# SchemaM02.net
KiCad netlist of a schematic drawn in Altium Designer
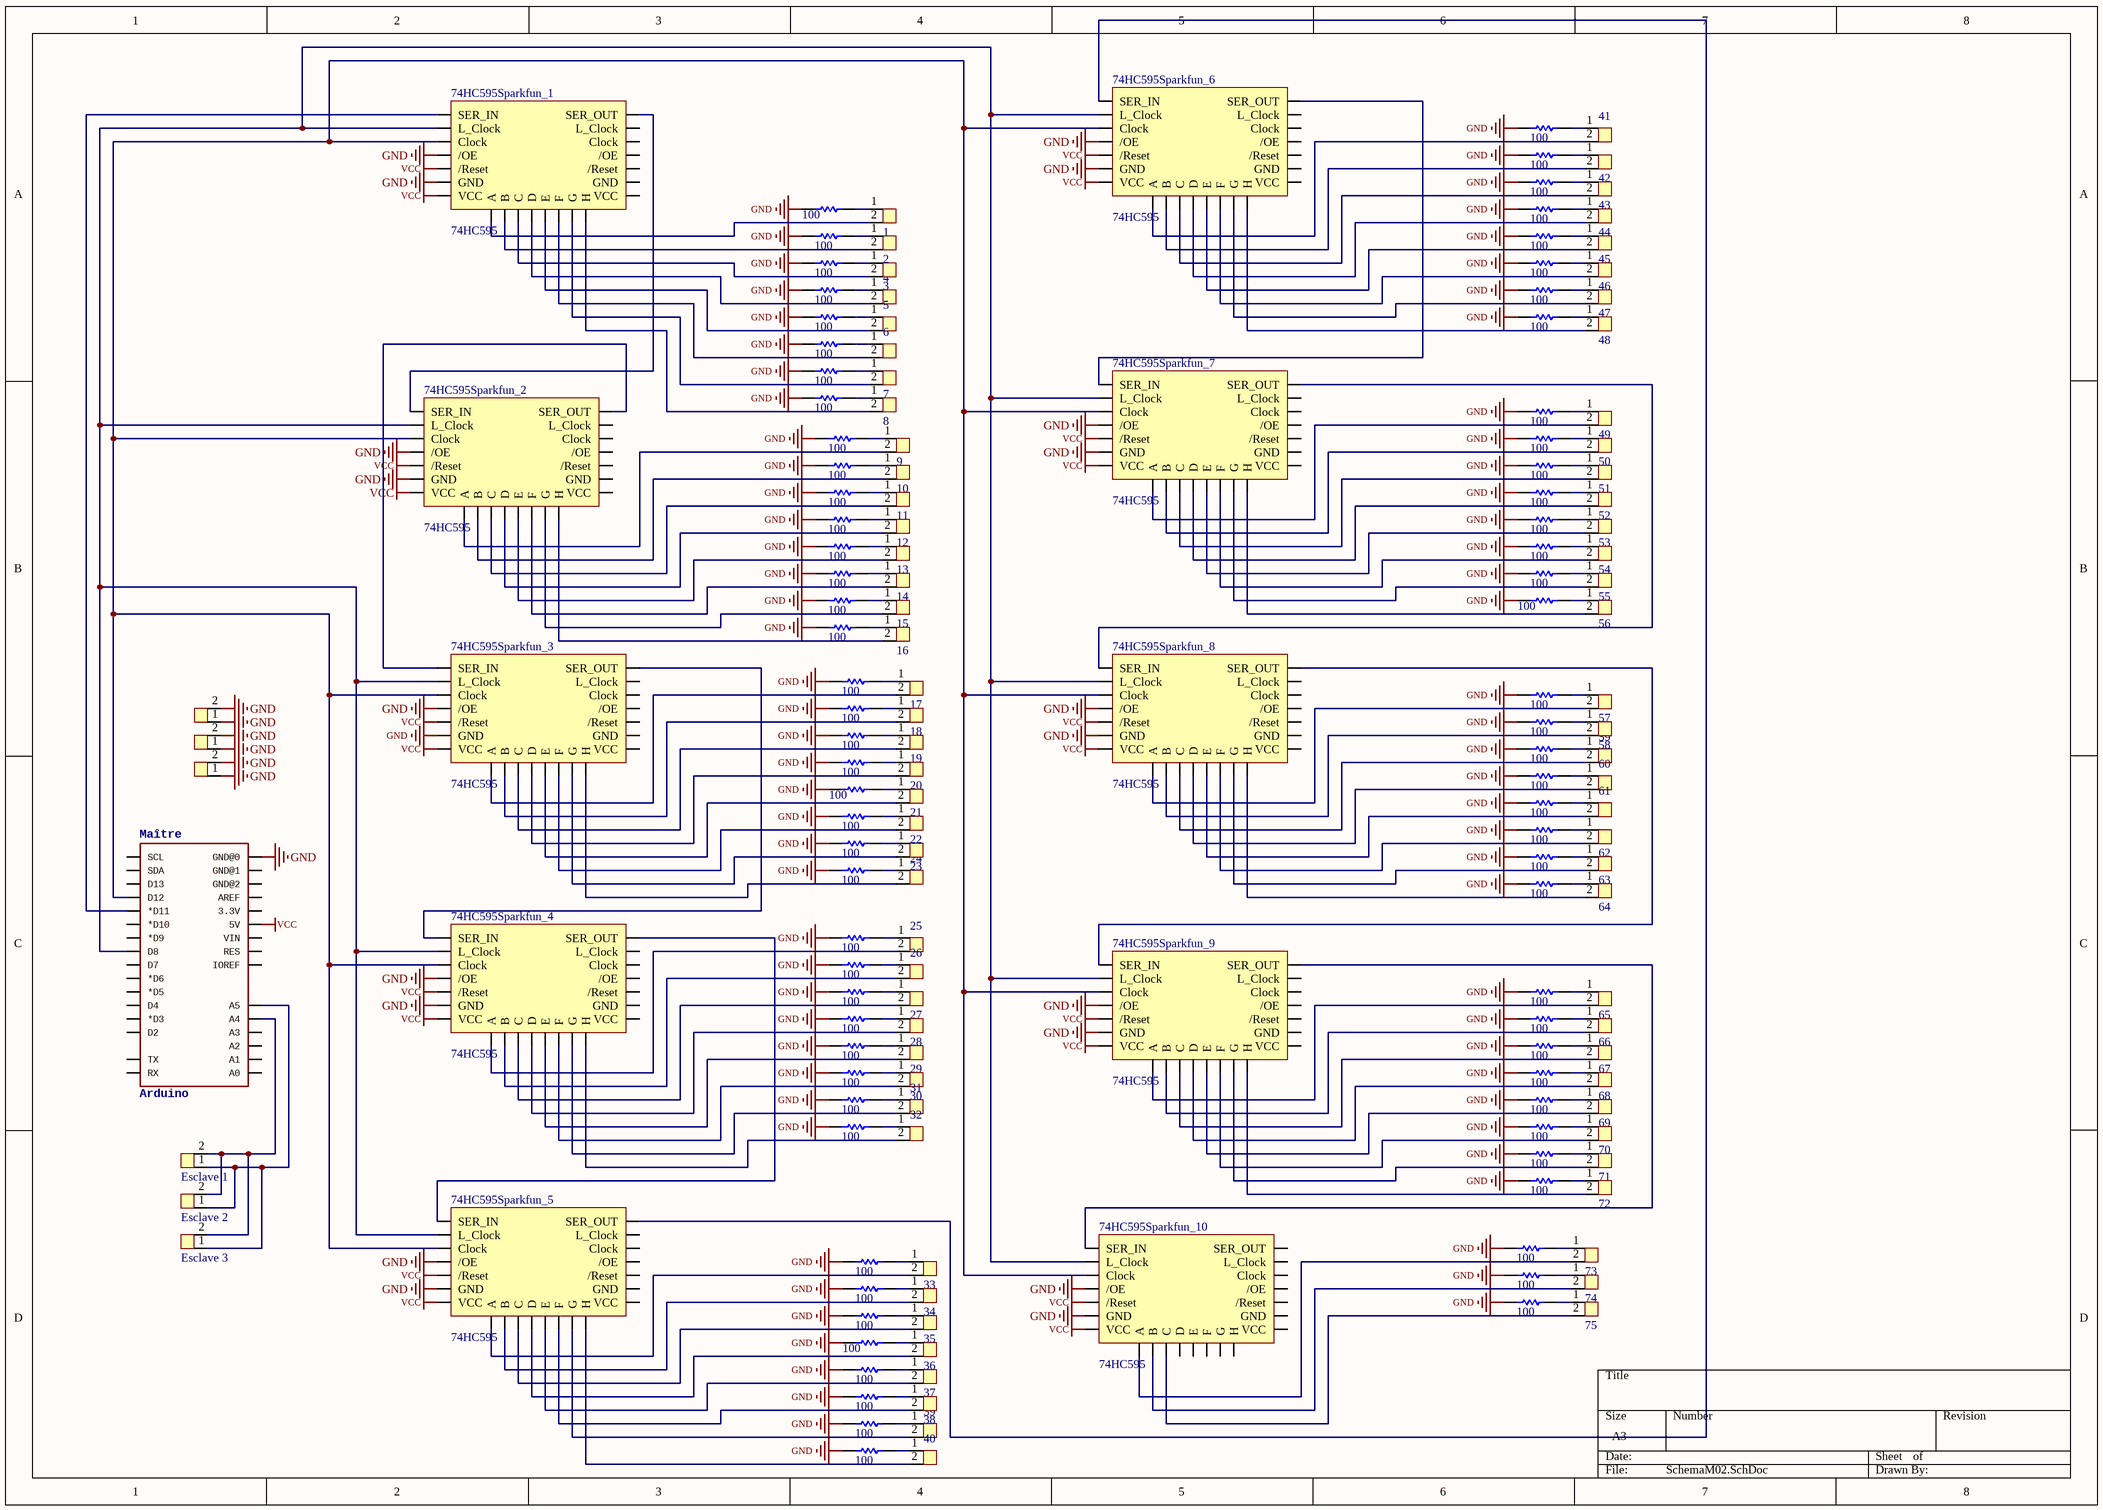
[diagram p0: SchemaM02.SchDoc]

(export (version "E")
  (design (tool "Eeschema 10.0.6"))
  (components
    (comp (ref "1")
      (value "Embase_CI_2_contacts")
      (footprint "Embase_CI_2_contacts")
      (libsource (lib "APISLibrary") (part "Embase_CI_2_contacts"))
    )
    (comp (ref "2")
      (value "Embase_CI_2_contacts")
      (footprint "Embase_CI_2_contacts")
      (libsource (lib "APISLibrary") (part "Embase_CI_2_contacts"))
    )
    (comp (ref "3")
      (value "Embase_CI_2_contacts")
      (footprint "Embase_CI_2_contacts")
      (libsource (lib "APISLibrary") (part "Embase_CI_2_contacts"))
    )
    (comp (ref "4")
      (value "Embase_CI_2_contacts")
      (footprint "Embase_CI_2_contacts")
      (libsource (lib "APISLibrary") (part "Embase_CI_2_contacts"))
    )
    (comp (ref "5")
      (value "Embase_CI_2_contacts")
      (footprint "Embase_CI_2_contacts")
      (libsource (lib "APISLibrary") (part "Embase_CI_2_contacts"))
    )
    (comp (ref "6")
      (value "Embase_CI_2_contacts")
      (footprint "Embase_CI_2_contacts")
      (libsource (lib "APISLibrary") (part "Embase_CI_2_contacts"))
    )
    (comp (ref "7")
      (value "Embase_CI_2_contacts")
      (footprint "Embase_CI_2_contacts")
      (libsource (lib "APISLibrary") (part "Embase_CI_2_contacts"))
    )
    (comp (ref "8")
      (value "Embase_CI_2_contacts")
      (footprint "Embase_CI_2_contacts")
      (libsource (lib "APISLibrary") (part "Embase_CI_2_contacts"))
    )
    (comp (ref "9")
      (value "Embase_CI_2_contacts")
      (footprint "Embase_CI_2_contacts")
      (libsource (lib "APISLibrary") (part "Embase_CI_2_contacts"))
    )
    (comp (ref "10")
      (value "Embase_CI_2_contacts")
      (footprint "Embase_CI_2_contacts")
      (libsource (lib "APISLibrary") (part "Embase_CI_2_contacts"))
    )
    (comp (ref "11")
      (value "Embase_CI_2_contacts")
      (footprint "Embase_CI_2_contacts")
      (libsource (lib "APISLibrary") (part "Embase_CI_2_contacts"))
    )
    (comp (ref "12")
      (value "Embase_CI_2_contacts")
      (footprint "Embase_CI_2_contacts")
      (libsource (lib "APISLibrary") (part "Embase_CI_2_contacts"))
    )
    (comp (ref "13")
      (value "Embase_CI_2_contacts")
      (footprint "Embase_CI_2_contacts")
      (libsource (lib "APISLibrary") (part "Embase_CI_2_contacts"))
    )
    (comp (ref "14")
      (value "Embase_CI_2_contacts")
      (footprint "Embase_CI_2_contacts")
      (libsource (lib "APISLibrary") (part "Embase_CI_2_contacts"))
    )
    (comp (ref "15")
      (value "Embase_CI_2_contacts")
      (footprint "Embase_CI_2_contacts")
      (libsource (lib "APISLibrary") (part "Embase_CI_2_contacts"))
    )
    (comp (ref "16")
      (value "Embase_CI_2_contacts")
      (footprint "Embase_CI_2_contacts")
      (libsource (lib "APISLibrary") (part "Embase_CI_2_contacts"))
    )
    (comp (ref "17")
      (value "Embase_CI_2_contacts")
      (footprint "Embase_CI_2_contacts")
      (libsource (lib "APISLibrary") (part "Embase_CI_2_contacts"))
    )
    (comp (ref "18")
      (value "Embase_CI_2_contacts")
      (footprint "Embase_CI_2_contacts")
      (libsource (lib "APISLibrary") (part "Embase_CI_2_contacts"))
    )
    (comp (ref "19")
      (value "Embase_CI_2_contacts")
      (footprint "Embase_CI_2_contacts")
      (libsource (lib "APISLibrary") (part "Embase_CI_2_contacts"))
    )
    (comp (ref "20")
      (value "Embase_CI_2_contacts")
      (footprint "Embase_CI_2_contacts")
      (libsource (lib "APISLibrary") (part "Embase_CI_2_contacts"))
    )
    (comp (ref "21")
      (value "Embase_CI_2_contacts")
      (footprint "Embase_CI_2_contacts")
      (libsource (lib "APISLibrary") (part "Embase_CI_2_contacts"))
    )
    (comp (ref "22")
      (value "Embase_CI_2_contacts")
      (footprint "Embase_CI_2_contacts")
      (libsource (lib "APISLibrary") (part "Embase_CI_2_contacts"))
    )
    (comp (ref "23")
      (value "Embase_CI_2_contacts")
      (footprint "Embase_CI_2_contacts")
      (libsource (lib "APISLibrary") (part "Embase_CI_2_contacts"))
    )
    (comp (ref "24")
      (value "Embase_CI_2_contacts")
      (footprint "Embase_CI_2_contacts")
      (libsource (lib "APISLibrary") (part "Embase_CI_2_contacts"))
    )
    (comp (ref "25")
      (value "Embase_CI_2_contacts")
      (footprint "Embase_CI_2_contacts")
      (libsource (lib "APISLibrary") (part "Embase_CI_2_contacts"))
    )
    (comp (ref "26")
      (value "Embase_CI_2_contacts")
      (footprint "Embase_CI_2_contacts")
      (libsource (lib "APISLibrary") (part "Embase_CI_2_contacts"))
    )
    (comp (ref "27")
      (value "Embase_CI_2_contacts")
      (footprint "Embase_CI_2_contacts")
      (libsource (lib "APISLibrary") (part "Embase_CI_2_contacts"))
    )
    (comp (ref "28")
      (value "Embase_CI_2_contacts")
      (footprint "Embase_CI_2_contacts")
      (libsource (lib "APISLibrary") (part "Embase_CI_2_contacts"))
    )
    (comp (ref "29")
      (value "Embase_CI_2_contacts")
      (footprint "Embase_CI_2_contacts")
      (libsource (lib "APISLibrary") (part "Embase_CI_2_contacts"))
    )
    (comp (ref "30")
      (value "Embase_CI_2_contacts")
      (footprint "Embase_CI_2_contacts")
      (libsource (lib "APISLibrary") (part "Embase_CI_2_contacts"))
    )
    (comp (ref "31")
      (value "Embase_CI_2_contacts")
      (footprint "Embase_CI_2_contacts")
      (libsource (lib "APISLibrary") (part "Embase_CI_2_contacts"))
    )
    (comp (ref "32")
      (value "Embase_CI_2_contacts")
      (footprint "Embase_CI_2_contacts")
      (libsource (lib "APISLibrary") (part "Embase_CI_2_contacts"))
    )
    (comp (ref "33")
      (value "Embase_CI_2_contacts")
      (footprint "Embase_CI_2_contacts")
      (libsource (lib "APISLibrary") (part "Embase_CI_2_contacts"))
    )
    (comp (ref "34")
      (value "Embase_CI_2_contacts")
      (footprint "Embase_CI_2_contacts")
      (libsource (lib "APISLibrary") (part "Embase_CI_2_contacts"))
    )
    (comp (ref "35")
      (value "Embase_CI_2_contacts")
      (footprint "Embase_CI_2_contacts")
      (libsource (lib "APISLibrary") (part "Embase_CI_2_contacts"))
    )
    (comp (ref "36")
      (value "Embase_CI_2_contacts")
      (footprint "Embase_CI_2_contacts")
      (libsource (lib "APISLibrary") (part "Embase_CI_2_contacts"))
    )
    (comp (ref "37")
      (value "Embase_CI_2_contacts")
      (footprint "Embase_CI_2_contacts")
      (libsource (lib "APISLibrary") (part "Embase_CI_2_contacts"))
    )
    (comp (ref "38")
      (value "Embase_CI_2_contacts")
      (footprint "Embase_CI_2_contacts")
      (libsource (lib "APISLibrary") (part "Embase_CI_2_contacts"))
    )
    (comp (ref "39")
      (value "Embase_CI_2_contacts")
      (footprint "Embase_CI_2_contacts")
      (libsource (lib "APISLibrary") (part "Embase_CI_2_contacts"))
    )
    (comp (ref "40")
      (value "Embase_CI_2_contacts")
      (footprint "Embase_CI_2_contacts")
      (libsource (lib "APISLibrary") (part "Embase_CI_2_contacts"))
    )
    (comp (ref "41")
      (value "Embase_CI_2_contacts")
      (footprint "Embase_CI_2_contacts")
      (libsource (lib "APISLibrary") (part "Embase_CI_2_contacts"))
    )
    (comp (ref "42")
      (value "Embase_CI_2_contacts")
      (footprint "Embase_CI_2_contacts")
      (libsource (lib "APISLibrary") (part "Embase_CI_2_contacts"))
    )
    (comp (ref "43")
      (value "Embase_CI_2_contacts")
      (footprint "Embase_CI_2_contacts")
      (libsource (lib "APISLibrary") (part "Embase_CI_2_contacts"))
    )
    (comp (ref "44")
      (value "Embase_CI_2_contacts")
      (footprint "Embase_CI_2_contacts")
      (libsource (lib "APISLibrary") (part "Embase_CI_2_contacts"))
    )
    (comp (ref "45")
      (value "Embase_CI_2_contacts")
      (footprint "Embase_CI_2_contacts")
      (libsource (lib "APISLibrary") (part "Embase_CI_2_contacts"))
    )
    (comp (ref "46")
      (value "Embase_CI_2_contacts")
      (footprint "Embase_CI_2_contacts")
      (libsource (lib "APISLibrary") (part "Embase_CI_2_contacts"))
    )
    (comp (ref "47")
      (value "Embase_CI_2_contacts")
      (footprint "Embase_CI_2_contacts")
      (libsource (lib "APISLibrary") (part "Embase_CI_2_contacts"))
    )
    (comp (ref "48")
      (value "Embase_CI_2_contacts")
      (footprint "Embase_CI_2_contacts")
      (libsource (lib "APISLibrary") (part "Embase_CI_2_contacts"))
    )
    (comp (ref "49")
      (value "Embase_CI_2_contacts")
      (footprint "Embase_CI_2_contacts")
      (libsource (lib "APISLibrary") (part "Embase_CI_2_contacts"))
    )
    (comp (ref "50")
      (value "Embase_CI_2_contacts")
      (footprint "Embase_CI_2_contacts")
      (libsource (lib "APISLibrary") (part "Embase_CI_2_contacts"))
    )
    (comp (ref "51")
      (value "Embase_CI_2_contacts")
      (footprint "Embase_CI_2_contacts")
      (libsource (lib "APISLibrary") (part "Embase_CI_2_contacts"))
    )
    (comp (ref "52")
      (value "Embase_CI_2_contacts")
      (footprint "Embase_CI_2_contacts")
      (libsource (lib "APISLibrary") (part "Embase_CI_2_contacts"))
    )
    (comp (ref "53")
      (value "Embase_CI_2_contacts")
      (footprint "Embase_CI_2_contacts")
      (libsource (lib "APISLibrary") (part "Embase_CI_2_contacts"))
    )
    (comp (ref "54")
      (value "Embase_CI_2_contacts")
      (footprint "Embase_CI_2_contacts")
      (libsource (lib "APISLibrary") (part "Embase_CI_2_contacts"))
    )
    (comp (ref "55")
      (value "Embase_CI_2_contacts")
      (footprint "Embase_CI_2_contacts")
      (libsource (lib "APISLibrary") (part "Embase_CI_2_contacts"))
    )
    (comp (ref "56")
      (value "Embase_CI_2_contacts")
      (footprint "Embase_CI_2_contacts")
      (libsource (lib "APISLibrary") (part "Embase_CI_2_contacts"))
    )
    (comp (ref "57")
      (value "Embase_CI_2_contacts")
      (footprint "Embase_CI_2_contacts")
      (libsource (lib "APISLibrary") (part "Embase_CI_2_contacts"))
    )
    (comp (ref "58")
      (value "Embase_CI_2_contacts")
      (footprint "Embase_CI_2_contacts")
      (libsource (lib "APISLibrary") (part "Embase_CI_2_contacts"))
    )
    (comp (ref "59")
      (value "Embase_CI_2_contacts")
      (footprint "Embase_CI_2_contacts")
      (libsource (lib "APISLibrary") (part "Embase_CI_2_contacts"))
    )
    (comp (ref "60")
      (value "Embase_CI_2_contacts")
      (footprint "Embase_CI_2_contacts")
      (libsource (lib "APISLibrary") (part "Embase_CI_2_contacts"))
    )
    (comp (ref "61")
      (value "Embase_CI_2_contacts")
      (footprint "Embase_CI_2_contacts")
      (libsource (lib "APISLibrary") (part "Embase_CI_2_contacts"))
    )
    (comp (ref "62")
      (value "Embase_CI_2_contacts")
      (footprint "Embase_CI_2_contacts")
      (libsource (lib "APISLibrary") (part "Embase_CI_2_contacts"))
    )
    (comp (ref "63")
      (value "Embase_CI_2_contacts")
      (footprint "Embase_CI_2_contacts")
      (libsource (lib "APISLibrary") (part "Embase_CI_2_contacts"))
    )
    (comp (ref "64")
      (value "Embase_CI_2_contacts")
      (footprint "Embase_CI_2_contacts")
      (libsource (lib "APISLibrary") (part "Embase_CI_2_contacts"))
    )
    (comp (ref "65")
      (value "Embase_CI_2_contacts")
      (footprint "Embase_CI_2_contacts")
      (libsource (lib "APISLibrary") (part "Embase_CI_2_contacts"))
    )
    (comp (ref "66")
      (value "Embase_CI_2_contacts")
      (footprint "Embase_CI_2_contacts")
      (libsource (lib "APISLibrary") (part "Embase_CI_2_contacts"))
    )
    (comp (ref "67")
      (value "Embase_CI_2_contacts")
      (footprint "Embase_CI_2_contacts")
      (libsource (lib "APISLibrary") (part "Embase_CI_2_contacts"))
    )
    (comp (ref "68")
      (value "Embase_CI_2_contacts")
      (footprint "Embase_CI_2_contacts")
      (libsource (lib "APISLibrary") (part "Embase_CI_2_contacts"))
    )
    (comp (ref "69")
      (value "Embase_CI_2_contacts")
      (footprint "Embase_CI_2_contacts")
      (libsource (lib "APISLibrary") (part "Embase_CI_2_contacts"))
    )
    (comp (ref "70")
      (value "Embase_CI_2_contacts")
      (footprint "Embase_CI_2_contacts")
      (libsource (lib "APISLibrary") (part "Embase_CI_2_contacts"))
    )
    (comp (ref "71")
      (value "Embase_CI_2_contacts")
      (footprint "Embase_CI_2_contacts")
      (libsource (lib "APISLibrary") (part "Embase_CI_2_contacts"))
    )
    (comp (ref "72")
      (value "Embase_CI_2_contacts")
      (footprint "Embase_CI_2_contacts")
      (libsource (lib "APISLibrary") (part "Embase_CI_2_contacts"))
    )
    (comp (ref "73")
      (value "Embase_CI_2_contacts")
      (footprint "Embase_CI_2_contacts")
      (libsource (lib "APISLibrary") (part "Embase_CI_2_contacts"))
    )
    (comp (ref "74")
      (value "Embase_CI_2_contacts")
      (footprint "Embase_CI_2_contacts")
      (libsource (lib "APISLibrary") (part "Embase_CI_2_contacts"))
    )
    (comp (ref "74HC595Sparkfun_1")
      (value "74HC595")
      (footprint "74HC595")
      (libsource (lib "APISLibrary") (part "74HC595"))
    )
    (comp (ref "74HC595Sparkfun_2")
      (value "74HC595")
      (footprint "74HC595")
      (libsource (lib "APISLibrary") (part "74HC595"))
    )
    (comp (ref "74HC595Sparkfun_3")
      (value "74HC595")
      (footprint "74HC595")
      (libsource (lib "APISLibrary") (part "74HC595"))
    )
    (comp (ref "74HC595Sparkfun_4")
      (value "74HC595")
      (footprint "74HC595")
      (libsource (lib "APISLibrary") (part "74HC595"))
    )
    (comp (ref "74HC595Sparkfun_5")
      (value "74HC595")
      (footprint "74HC595")
      (libsource (lib "APISLibrary") (part "74HC595"))
    )
    (comp (ref "74HC595Sparkfun_6")
      (value "74HC595")
      (footprint "74HC595")
      (libsource (lib "APISLibrary") (part "74HC595"))
    )
    (comp (ref "74HC595Sparkfun_7")
      (value "74HC595")
      (footprint "74HC595")
      (libsource (lib "APISLibrary") (part "74HC595"))
    )
    (comp (ref "74HC595Sparkfun_8")
      (value "74HC595")
      (footprint "74HC595")
      (libsource (lib "APISLibrary") (part "74HC595"))
    )
    (comp (ref "74HC595Sparkfun_9")
      (value "74HC595")
      (footprint "74HC595")
      (libsource (lib "APISLibrary") (part "74HC595"))
    )
    (comp (ref "74HC595Sparkfun_10")
      (value "74HC595")
      (footprint "74HC595")
      (libsource (lib "APISLibrary") (part "74HC595"))
    )
    (comp (ref "75")
      (value "Embase_CI_2_contacts")
      (footprint "Embase_CI_2_contacts")
      (libsource (lib "APISLibrary") (part "Embase_CI_2_contacts"))
    )
    (comp (ref "Esclave 1")
      (value "Embase_CI_2_contacts")
      (footprint "Embase_CI_2_contacts")
      (libsource (lib "") (part "Embase_CI_2_contacts_1"))
    )
    (comp (ref "Esclave 2")
      (value "Embase_CI_2_contacts")
      (footprint "Embase_CI_2_contacts")
      (libsource (lib "") (part "Embase_CI_2_contacts_1"))
    )
    (comp (ref "Esclave 3")
      (value "Embase_CI_2_contacts")
      (footprint "Embase_CI_2_contacts")
      (libsource (lib "") (part "Embase_CI_2_contacts_1"))
    )
    (comp (ref "Esclave 4")
      (value "Embase_CI_2_contacts")
      (footprint "Embase_CI_2_contacts")
      (libsource (lib "") (part "Embase_CI_2_contacts_1"))
    )
    (comp (ref "Esclave 5")
      (value "Embase_CI_2_contacts")
      (footprint "Embase_CI_2_contacts")
      (libsource (lib "") (part "Embase_CI_2_contacts_1"))
    )
    (comp (ref "Esclave 6")
      (value "Embase_CI_2_contacts")
      (footprint "Embase_CI_2_contacts")
      (libsource (lib "") (part "Embase_CI_2_contacts_1"))
    )
    (comp (ref "Maître")
      (value "Arduino")
      (footprint "UNO_R3_SHIELD")
      (libsource (lib "SparkFun-Boards") (part "ARDUINO_R3_SHIELD"))
    )
    (comp (ref "R1")
      (value "100")
      (footprint "AXIAL-0.3")
      (description "Resistor")
      (fields (field (name "Comment") "Res1") (field (name "PUBLISHER") "Altium Limited"))
      (libsource (lib "Miscellaneous Devices") (part "Res1"))
    )
    (comp (ref "R2")
      (value "100")
      (footprint "AXIAL-0.3")
      (description "Resistor")
      (fields (field (name "Comment") "Res1") (field (name "PUBLISHER") "Altium Limited"))
      (libsource (lib "Miscellaneous Devices") (part "Res1"))
    )
    (comp (ref "R3")
      (value "100")
      (footprint "AXIAL-0.3")
      (description "Resistor")
      (fields (field (name "Comment") "Res1") (field (name "PUBLISHER") "Altium Limited"))
      (libsource (lib "Miscellaneous Devices") (part "Res1"))
    )
    (comp (ref "R4")
      (value "100")
      (footprint "AXIAL-0.3")
      (description "Resistor")
      (fields (field (name "Comment") "Res1") (field (name "PUBLISHER") "Altium Limited"))
      (libsource (lib "Miscellaneous Devices") (part "Res1"))
    )
    (comp (ref "R5")
      (value "100")
      (footprint "AXIAL-0.3")
      (description "Resistor")
      (fields (field (name "Comment") "Res1") (field (name "PUBLISHER") "Altium Limited"))
      (libsource (lib "Miscellaneous Devices") (part "Res1"))
    )
    (comp (ref "R6")
      (value "100")
      (footprint "AXIAL-0.3")
      (description "Resistor")
      (fields (field (name "Comment") "Res1") (field (name "PUBLISHER") "Altium Limited"))
      (libsource (lib "Miscellaneous Devices") (part "Res1"))
    )
    (comp (ref "R7")
      (value "100")
      (footprint "AXIAL-0.3")
      (description "Resistor")
      (fields (field (name "Comment") "Res1") (field (name "PUBLISHER") "Altium Limited"))
      (libsource (lib "Miscellaneous Devices") (part "Res1"))
    )
    (comp (ref "R8")
      (value "100")
      (footprint "AXIAL-0.3")
      (description "Resistor")
      (fields (field (name "Comment") "Res1") (field (name "PUBLISHER") "Altium Limited"))
      (libsource (lib "Miscellaneous Devices") (part "Res1"))
    )
    (comp (ref "R9")
      (value "100")
      (footprint "AXIAL-0.3")
      (description "Resistor")
      (fields (field (name "Comment") "Res1") (field (name "PUBLISHER") "Altium Limited"))
      (libsource (lib "Miscellaneous Devices") (part "Res1"))
    )
    (comp (ref "R10")
      (value "100")
      (footprint "AXIAL-0.3")
      (description "Resistor")
      (fields (field (name "Comment") "Res1") (field (name "PUBLISHER") "Altium Limited"))
      (libsource (lib "Miscellaneous Devices") (part "Res1"))
    )
    (comp (ref "R11")
      (value "100")
      (footprint "AXIAL-0.3")
      (description "Resistor")
      (fields (field (name "Comment") "Res1") (field (name "PUBLISHER") "Altium Limited"))
      (libsource (lib "Miscellaneous Devices") (part "Res1"))
    )
    (comp (ref "R12")
      (value "100")
      (footprint "AXIAL-0.3")
      (description "Resistor")
      (fields (field (name "Comment") "Res1") (field (name "PUBLISHER") "Altium Limited"))
      (libsource (lib "Miscellaneous Devices") (part "Res1"))
    )
    (comp (ref "R13")
      (value "100")
      (footprint "AXIAL-0.3")
      (description "Resistor")
      (fields (field (name "Comment") "Res1") (field (name "PUBLISHER") "Altium Limited"))
      (libsource (lib "Miscellaneous Devices") (part "Res1"))
    )
    (comp (ref "R14")
      (value "100")
      (footprint "AXIAL-0.3")
      (description "Resistor")
      (fields (field (name "Comment") "Res1") (field (name "PUBLISHER") "Altium Limited"))
      (libsource (lib "Miscellaneous Devices") (part "Res1"))
    )
    (comp (ref "R15")
      (value "100")
      (footprint "AXIAL-0.3")
      (description "Resistor")
      (fields (field (name "Comment") "Res1") (field (name "PUBLISHER") "Altium Limited"))
      (libsource (lib "Miscellaneous Devices") (part "Res1"))
    )
    (comp (ref "R16")
      (value "100")
      (footprint "AXIAL-0.3")
      (description "Resistor")
      (fields (field (name "Comment") "Res1") (field (name "PUBLISHER") "Altium Limited"))
      (libsource (lib "Miscellaneous Devices") (part "Res1"))
    )
    (comp (ref "R17")
      (value "100")
      (footprint "AXIAL-0.3")
      (description "Resistor")
      (fields (field (name "Comment") "Res1") (field (name "PUBLISHER") "Altium Limited"))
      (libsource (lib "Miscellaneous Devices") (part "Res1"))
    )
    (comp (ref "R18")
      (value "100")
      (footprint "AXIAL-0.3")
      (description "Resistor")
      (fields (field (name "Comment") "Res1") (field (name "PUBLISHER") "Altium Limited"))
      (libsource (lib "Miscellaneous Devices") (part "Res1"))
    )
    (comp (ref "R19")
      (value "100")
      (footprint "AXIAL-0.3")
      (description "Resistor")
      (fields (field (name "Comment") "Res1") (field (name "PUBLISHER") "Altium Limited"))
      (libsource (lib "Miscellaneous Devices") (part "Res1"))
    )
    (comp (ref "R20")
      (value "100")
      (footprint "AXIAL-0.3")
      (description "Resistor")
      (fields (field (name "Comment") "Res1") (field (name "PUBLISHER") "Altium Limited"))
      (libsource (lib "Miscellaneous Devices") (part "Res1"))
    )
    (comp (ref "R21")
      (value "100")
      (footprint "AXIAL-0.3")
      (description "Resistor")
      (fields (field (name "Comment") "Res1") (field (name "PUBLISHER") "Altium Limited"))
      (libsource (lib "Miscellaneous Devices") (part "Res1"))
    )
    (comp (ref "R22")
      (value "100")
      (footprint "AXIAL-0.3")
      (description "Resistor")
      (fields (field (name "Comment") "Res1") (field (name "PUBLISHER") "Altium Limited"))
      (libsource (lib "Miscellaneous Devices") (part "Res1"))
    )
    (comp (ref "R23")
      (value "100")
      (footprint "AXIAL-0.3")
      (description "Resistor")
      (fields (field (name "Comment") "Res1") (field (name "PUBLISHER") "Altium Limited"))
      (libsource (lib "Miscellaneous Devices") (part "Res1"))
    )
    (comp (ref "R24")
      (value "100")
      (footprint "AXIAL-0.3")
      (description "Resistor")
      (fields (field (name "Comment") "Res1") (field (name "PUBLISHER") "Altium Limited"))
      (libsource (lib "Miscellaneous Devices") (part "Res1"))
    )
    (comp (ref "R25")
      (value "100")
      (footprint "AXIAL-0.3")
      (description "Resistor")
      (fields (field (name "Comment") "Res1") (field (name "PUBLISHER") "Altium Limited"))
      (libsource (lib "Miscellaneous Devices") (part "Res1"))
    )
    (comp (ref "R26")
      (value "100")
      (footprint "AXIAL-0.3")
      (description "Resistor")
      (fields (field (name "Comment") "Res1") (field (name "PUBLISHER") "Altium Limited"))
      (libsource (lib "Miscellaneous Devices") (part "Res1"))
    )
    (comp (ref "R27")
      (value "100")
      (footprint "AXIAL-0.3")
      (description "Resistor")
      (fields (field (name "Comment") "Res1") (field (name "PUBLISHER") "Altium Limited"))
      (libsource (lib "Miscellaneous Devices") (part "Res1"))
    )
    (comp (ref "R28")
      (value "100")
      (footprint "AXIAL-0.3")
      (description "Resistor")
      (fields (field (name "Comment") "Res1") (field (name "PUBLISHER") "Altium Limited"))
      (libsource (lib "Miscellaneous Devices") (part "Res1"))
    )
    (comp (ref "R29")
      (value "100")
      (footprint "AXIAL-0.3")
      (description "Resistor")
      (fields (field (name "Comment") "Res1") (field (name "PUBLISHER") "Altium Limited"))
      (libsource (lib "Miscellaneous Devices") (part "Res1"))
    )
    (comp (ref "R30")
      (value "100")
      (footprint "AXIAL-0.3")
      (description "Resistor")
      (fields (field (name "Comment") "Res1") (field (name "PUBLISHER") "Altium Limited"))
      (libsource (lib "Miscellaneous Devices") (part "Res1"))
    )
    (comp (ref "R31")
      (value "100")
      (footprint "AXIAL-0.3")
      (description "Resistor")
      (fields (field (name "Comment") "Res1") (field (name "PUBLISHER") "Altium Limited"))
      (libsource (lib "Miscellaneous Devices") (part "Res1"))
    )
    (comp (ref "R32")
      (value "100")
      (footprint "AXIAL-0.3")
      (description "Resistor")
      (fields (field (name "Comment") "Res1") (field (name "PUBLISHER") "Altium Limited"))
      (libsource (lib "Miscellaneous Devices") (part "Res1"))
    )
    (comp (ref "R33")
      (value "100")
      (footprint "AXIAL-0.3")
      (description "Resistor")
      (fields (field (name "Comment") "Res1") (field (name "PUBLISHER") "Altium Limited"))
      (libsource (lib "Miscellaneous Devices") (part "Res1"))
    )
    (comp (ref "R34")
      (value "100")
      (footprint "AXIAL-0.3")
      (description "Resistor")
      (fields (field (name "Comment") "Res1") (field (name "PUBLISHER") "Altium Limited"))
      (libsource (lib "Miscellaneous Devices") (part "Res1"))
    )
    (comp (ref "R35")
      (value "100")
      (footprint "AXIAL-0.3")
      (description "Resistor")
      (fields (field (name "Comment") "Res1") (field (name "PUBLISHER") "Altium Limited"))
      (libsource (lib "Miscellaneous Devices") (part "Res1"))
    )
    (comp (ref "R36")
      (value "100")
      (footprint "AXIAL-0.3")
      (description "Resistor")
      (fields (field (name "Comment") "Res1") (field (name "PUBLISHER") "Altium Limited"))
      (libsource (lib "Miscellaneous Devices") (part "Res1"))
    )
    (comp (ref "R37")
      (value "100")
      (footprint "AXIAL-0.3")
      (description "Resistor")
      (fields (field (name "Comment") "Res1") (field (name "PUBLISHER") "Altium Limited"))
      (libsource (lib "Miscellaneous Devices") (part "Res1"))
    )
    (comp (ref "R38")
      (value "100")
      (footprint "AXIAL-0.3")
      (description "Resistor")
      (fields (field (name "Comment") "Res1") (field (name "PUBLISHER") "Altium Limited"))
      (libsource (lib "Miscellaneous Devices") (part "Res1"))
    )
    (comp (ref "R39")
      (value "100")
      (footprint "AXIAL-0.3")
      (description "Resistor")
      (fields (field (name "Comment") "Res1") (field (name "PUBLISHER") "Altium Limited"))
      (libsource (lib "Miscellaneous Devices") (part "Res1"))
    )
    (comp (ref "R40")
      (value "100")
      (footprint "AXIAL-0.3")
      (description "Resistor")
      (fields (field (name "Comment") "Res1") (field (name "PUBLISHER") "Altium Limited"))
      (libsource (lib "Miscellaneous Devices") (part "Res1"))
    )
    (comp (ref "R41")
      (value "100")
      (footprint "AXIAL-0.3")
      (description "Resistor")
      (fields (field (name "Comment") "Res1") (field (name "PUBLISHER") "Altium Limited"))
      (libsource (lib "Miscellaneous Devices") (part "Res1"))
    )
    (comp (ref "R42")
      (value "100")
      (footprint "AXIAL-0.3")
      (description "Resistor")
      (fields (field (name "Comment") "Res1") (field (name "PUBLISHER") "Altium Limited"))
      (libsource (lib "Miscellaneous Devices") (part "Res1"))
    )
    (comp (ref "R43")
      (value "100")
      (footprint "AXIAL-0.3")
      (description "Resistor")
      (fields (field (name "Comment") "Res1") (field (name "PUBLISHER") "Altium Limited"))
      (libsource (lib "Miscellaneous Devices") (part "Res1"))
    )
    (comp (ref "R44")
      (value "100")
      (footprint "AXIAL-0.3")
      (description "Resistor")
      (fields (field (name "Comment") "Res1") (field (name "PUBLISHER") "Altium Limited"))
      (libsource (lib "Miscellaneous Devices") (part "Res1"))
    )
    (comp (ref "R45")
      (value "100")
      (footprint "AXIAL-0.3")
      (description "Resistor")
      (fields (field (name "Comment") "Res1") (field (name "PUBLISHER") "Altium Limited"))
      (libsource (lib "Miscellaneous Devices") (part "Res1"))
    )
    (comp (ref "R46")
      (value "100")
      (footprint "AXIAL-0.3")
      (description "Resistor")
      (fields (field (name "Comment") "Res1") (field (name "PUBLISHER") "Altium Limited"))
      (libsource (lib "Miscellaneous Devices") (part "Res1"))
    )
    (comp (ref "R47")
      (value "100")
      (footprint "AXIAL-0.3")
      (description "Resistor")
      (fields (field (name "Comment") "Res1") (field (name "PUBLISHER") "Altium Limited"))
      (libsource (lib "Miscellaneous Devices") (part "Res1"))
    )
    (comp (ref "R48")
      (value "100")
      (footprint "AXIAL-0.3")
      (description "Resistor")
      (fields (field (name "Comment") "Res1") (field (name "PUBLISHER") "Altium Limited"))
      (libsource (lib "Miscellaneous Devices") (part "Res1"))
    )
    (comp (ref "R49")
      (value "100")
      (footprint "AXIAL-0.3")
      (description "Resistor")
      (fields (field (name "Comment") "Res1") (field (name "PUBLISHER") "Altium Limited"))
      (libsource (lib "Miscellaneous Devices") (part "Res1"))
    )
    (comp (ref "R50")
      (value "100")
      (footprint "AXIAL-0.3")
      (description "Resistor")
      (fields (field (name "Comment") "Res1") (field (name "PUBLISHER") "Altium Limited"))
      (libsource (lib "Miscellaneous Devices") (part "Res1"))
    )
    (comp (ref "R51")
      (value "100")
      (footprint "AXIAL-0.3")
      (description "Resistor")
      (fields (field (name "Comment") "Res1") (field (name "PUBLISHER") "Altium Limited"))
      (libsource (lib "Miscellaneous Devices") (part "Res1"))
    )
    (comp (ref "R52")
      (value "100")
      (footprint "AXIAL-0.3")
      (description "Resistor")
      (fields (field (name "Comment") "Res1") (field (name "PUBLISHER") "Altium Limited"))
      (libsource (lib "Miscellaneous Devices") (part "Res1"))
    )
    (comp (ref "R53")
      (value "100")
      (footprint "AXIAL-0.3")
      (description "Resistor")
      (fields (field (name "Comment") "Res1") (field (name "PUBLISHER") "Altium Limited"))
      (libsource (lib "Miscellaneous Devices") (part "Res1"))
    )
    (comp (ref "R54")
      (value "100")
      (footprint "AXIAL-0.3")
      (description "Resistor")
      (fields (field (name "Comment") "Res1") (field (name "PUBLISHER") "Altium Limited"))
      (libsource (lib "Miscellaneous Devices") (part "Res1"))
    )
    (comp (ref "R55")
      (value "100")
      (footprint "AXIAL-0.3")
      (description "Resistor")
      (fields (field (name "Comment") "Res1") (field (name "PUBLISHER") "Altium Limited"))
      (libsource (lib "Miscellaneous Devices") (part "Res1"))
    )
    (comp (ref "R56")
      (value "100")
      (footprint "AXIAL-0.3")
      (description "Resistor")
      (fields (field (name "Comment") "Res1") (field (name "PUBLISHER") "Altium Limited"))
      (libsource (lib "Miscellaneous Devices") (part "Res1"))
    )
    (comp (ref "R57")
      (value "100")
      (footprint "AXIAL-0.3")
      (description "Resistor")
      (fields (field (name "Comment") "Res1") (field (name "PUBLISHER") "Altium Limited"))
      (libsource (lib "Miscellaneous Devices") (part "Res1"))
    )
    (comp (ref "R58")
      (value "100")
      (footprint "AXIAL-0.3")
      (description "Resistor")
      (fields (field (name "Comment") "Res1") (field (name "PUBLISHER") "Altium Limited"))
      (libsource (lib "Miscellaneous Devices") (part "Res1"))
    )
    (comp (ref "R59")
      (value "100")
      (footprint "AXIAL-0.3")
      (description "Resistor")
      (fields (field (name "Comment") "Res1") (field (name "PUBLISHER") "Altium Limited"))
      (libsource (lib "Miscellaneous Devices") (part "Res1"))
    )
    (comp (ref "R60")
      (value "100")
      (footprint "AXIAL-0.3")
      (description "Resistor")
      (fields (field (name "Comment") "Res1") (field (name "PUBLISHER") "Altium Limited"))
      (libsource (lib "Miscellaneous Devices") (part "Res1"))
    )
    (comp (ref "R61")
      (value "100")
      (footprint "AXIAL-0.3")
      (description "Resistor")
      (fields (field (name "Comment") "Res1") (field (name "PUBLISHER") "Altium Limited"))
      (libsource (lib "Miscellaneous Devices") (part "Res1"))
    )
    (comp (ref "R62")
      (value "100")
      (footprint "AXIAL-0.3")
      (description "Resistor")
      (fields (field (name "Comment") "Res1") (field (name "PUBLISHER") "Altium Limited"))
      (libsource (lib "Miscellaneous Devices") (part "Res1"))
    )
    (comp (ref "R63")
      (value "100")
      (footprint "AXIAL-0.3")
      (description "Resistor")
      (fields (field (name "Comment") "Res1") (field (name "PUBLISHER") "Altium Limited"))
      (libsource (lib "Miscellaneous Devices") (part "Res1"))
    )
    (comp (ref "R64")
      (value "100")
      (footprint "AXIAL-0.3")
      (description "Resistor")
      (fields (field (name "Comment") "Res1") (field (name "PUBLISHER") "Altium Limited"))
      (libsource (lib "Miscellaneous Devices") (part "Res1"))
    )
    (comp (ref "R65")
      (value "100")
      (footprint "AXIAL-0.3")
      (description "Resistor")
      (fields (field (name "Comment") "Res1") (field (name "PUBLISHER") "Altium Limited"))
      (libsource (lib "Miscellaneous Devices") (part "Res1"))
    )
    (comp (ref "R66")
      (value "100")
      (footprint "AXIAL-0.3")
      (description "Resistor")
      (fields (field (name "Comment") "Res1") (field (name "PUBLISHER") "Altium Limited"))
      (libsource (lib "Miscellaneous Devices") (part "Res1"))
    )
    (comp (ref "R67")
      (value "100")
      (footprint "AXIAL-0.3")
      (description "Resistor")
      (fields (field (name "Comment") "Res1") (field (name "PUBLISHER") "Altium Limited"))
      (libsource (lib "Miscellaneous Devices") (part "Res1"))
    )
    (comp (ref "R68")
      (value "100")
      (footprint "AXIAL-0.3")
      (description "Resistor")
      (fields (field (name "Comment") "Res1") (field (name "PUBLISHER") "Altium Limited"))
      (libsource (lib "Miscellaneous Devices") (part "Res1"))
    )
    (comp (ref "R69")
      (value "100")
      (footprint "AXIAL-0.3")
      (description "Resistor")
      (fields (field (name "Comment") "Res1") (field (name "PUBLISHER") "Altium Limited"))
      (libsource (lib "Miscellaneous Devices") (part "Res1"))
    )
    (comp (ref "R70")
      (value "100")
      (footprint "AXIAL-0.3")
      (description "Resistor")
      (fields (field (name "Comment") "Res1") (field (name "PUBLISHER") "Altium Limited"))
      (libsource (lib "Miscellaneous Devices") (part "Res1"))
    )
    (comp (ref "R71")
      (value "100")
      (footprint "AXIAL-0.3")
      (description "Resistor")
      (fields (field (name "Comment") "Res1") (field (name "PUBLISHER") "Altium Limited"))
      (libsource (lib "Miscellaneous Devices") (part "Res1"))
    )
    (comp (ref "R72")
      (value "100")
      (footprint "AXIAL-0.3")
      (description "Resistor")
      (fields (field (name "Comment") "Res1") (field (name "PUBLISHER") "Altium Limited"))
      (libsource (lib "Miscellaneous Devices") (part "Res1"))
    )
    (comp (ref "R73")
      (value "100")
      (footprint "AXIAL-0.3")
      (description "Resistor")
      (fields (field (name "Comment") "Res1") (field (name "PUBLISHER") "Altium Limited"))
      (libsource (lib "Miscellaneous Devices") (part "Res1"))
    )
    (comp (ref "R74")
      (value "100")
      (footprint "AXIAL-0.3")
      (description "Resistor")
      (fields (field (name "Comment") "Res1") (field (name "PUBLISHER") "Altium Limited"))
      (libsource (lib "Miscellaneous Devices") (part "Res1"))
    )
    (comp (ref "R75")
      (value "100")
      (footprint "AXIAL-0.3")
      (description "Resistor")
      (fields (field (name "Comment") "Res1") (field (name "PUBLISHER") "Altium Limited"))
      (libsource (lib "Miscellaneous Devices") (part "Res1"))
    )
  )
  (nets
    (net (code "1") (name "GND") (class "Default")
      (node (ref "74HC595Sparkfun_1") (pin "2") (pinfunction "GND_2") (pintype "passive"))
      (node (ref "74HC595Sparkfun_1") (pin "4") (pinfunction "/OE_4") (pintype "passive"))
      (node (ref "74HC595Sparkfun_10") (pin "2") (pinfunction "GND_2") (pintype "passive"))
      (node (ref "74HC595Sparkfun_10") (pin "4") (pinfunction "/OE_4") (pintype "passive"))
      (node (ref "74HC595Sparkfun_2") (pin "2") (pinfunction "GND_2") (pintype "passive"))
      (node (ref "74HC595Sparkfun_2") (pin "4") (pinfunction "/OE_4") (pintype "passive"))
      (node (ref "74HC595Sparkfun_3") (pin "2") (pinfunction "GND_2") (pintype "passive"))
      (node (ref "74HC595Sparkfun_3") (pin "4") (pinfunction "/OE_4") (pintype "passive"))
      (node (ref "74HC595Sparkfun_4") (pin "2") (pinfunction "GND_2") (pintype "passive"))
      (node (ref "74HC595Sparkfun_4") (pin "4") (pinfunction "/OE_4") (pintype "passive"))
      (node (ref "74HC595Sparkfun_5") (pin "2") (pinfunction "GND_2") (pintype "passive"))
      (node (ref "74HC595Sparkfun_5") (pin "4") (pinfunction "/OE_4") (pintype "passive"))
      (node (ref "74HC595Sparkfun_6") (pin "2") (pinfunction "GND_2") (pintype "passive"))
      (node (ref "74HC595Sparkfun_6") (pin "4") (pinfunction "/OE_4") (pintype "passive"))
      (node (ref "74HC595Sparkfun_7") (pin "2") (pinfunction "GND_2") (pintype "passive"))
      (node (ref "74HC595Sparkfun_7") (pin "4") (pinfunction "/OE_4") (pintype "passive"))
      (node (ref "74HC595Sparkfun_8") (pin "2") (pinfunction "GND_2") (pintype "passive"))
      (node (ref "74HC595Sparkfun_8") (pin "4") (pinfunction "/OE_4") (pintype "passive"))
      (node (ref "74HC595Sparkfun_9") (pin "2") (pinfunction "GND_2") (pintype "passive"))
      (node (ref "74HC595Sparkfun_9") (pin "4") (pinfunction "/OE_4") (pintype "passive"))
      (node (ref "Esclave 4") (pin "1") (pinfunction "1_1") (pintype "passive"))
      (node (ref "Esclave 4") (pin "2") (pinfunction "2_2") (pintype "passive"))
      (node (ref "Esclave 5") (pin "1") (pinfunction "1_1") (pintype "passive"))
      (node (ref "Esclave 5") (pin "2") (pinfunction "2_2") (pintype "passive"))
      (node (ref "Esclave 6") (pin "1") (pinfunction "1_1") (pintype "passive"))
      (node (ref "Esclave 6") (pin "2") (pinfunction "2_2") (pintype "passive"))
      (node (ref "Maître") (pin "GND@0") (pinfunction "GND@0_GND@0") (pintype "passive"))
      (node (ref "R1") (pin "1") (pinfunction "1_1") (pintype "passive"))
      (node (ref "R10") (pin "1") (pinfunction "1_1") (pintype "passive"))
      (node (ref "R11") (pin "1") (pinfunction "1_1") (pintype "passive"))
      (node (ref "R12") (pin "1") (pinfunction "1_1") (pintype "passive"))
      (node (ref "R13") (pin "1") (pinfunction "1_1") (pintype "passive"))
      (node (ref "R14") (pin "1") (pinfunction "1_1") (pintype "passive"))
      (node (ref "R15") (pin "1") (pinfunction "1_1") (pintype "passive"))
      (node (ref "R16") (pin "1") (pinfunction "1_1") (pintype "passive"))
      (node (ref "R17") (pin "1") (pinfunction "1_1") (pintype "passive"))
      (node (ref "R18") (pin "1") (pinfunction "1_1") (pintype "passive"))
      (node (ref "R19") (pin "1") (pinfunction "1_1") (pintype "passive"))
      (node (ref "R2") (pin "1") (pinfunction "1_1") (pintype "passive"))
      (node (ref "R20") (pin "1") (pinfunction "1_1") (pintype "passive"))
      (node (ref "R21") (pin "1") (pinfunction "1_1") (pintype "passive"))
      (node (ref "R22") (pin "1") (pinfunction "1_1") (pintype "passive"))
      (node (ref "R23") (pin "1") (pinfunction "1_1") (pintype "passive"))
      (node (ref "R24") (pin "1") (pinfunction "1_1") (pintype "passive"))
      (node (ref "R25") (pin "1") (pinfunction "1_1") (pintype "passive"))
      (node (ref "R26") (pin "1") (pinfunction "1_1") (pintype "passive"))
      (node (ref "R27") (pin "1") (pinfunction "1_1") (pintype "passive"))
      (node (ref "R28") (pin "1") (pinfunction "1_1") (pintype "passive"))
      (node (ref "R29") (pin "1") (pinfunction "1_1") (pintype "passive"))
      (node (ref "R3") (pin "1") (pinfunction "1_1") (pintype "passive"))
      (node (ref "R30") (pin "1") (pinfunction "1_1") (pintype "passive"))
      (node (ref "R31") (pin "1") (pinfunction "1_1") (pintype "passive"))
      (node (ref "R32") (pin "1") (pinfunction "1_1") (pintype "passive"))
      (node (ref "R33") (pin "1") (pinfunction "1_1") (pintype "passive"))
      (node (ref "R34") (pin "1") (pinfunction "1_1") (pintype "passive"))
      (node (ref "R35") (pin "1") (pinfunction "1_1") (pintype "passive"))
      (node (ref "R36") (pin "1") (pinfunction "1_1") (pintype "passive"))
      (node (ref "R37") (pin "1") (pinfunction "1_1") (pintype "passive"))
      (node (ref "R38") (pin "1") (pinfunction "1_1") (pintype "passive"))
      (node (ref "R39") (pin "1") (pinfunction "1_1") (pintype "passive"))
      (node (ref "R4") (pin "1") (pinfunction "1_1") (pintype "passive"))
      (node (ref "R40") (pin "1") (pinfunction "1_1") (pintype "passive"))
      (node (ref "R41") (pin "1") (pinfunction "1_1") (pintype "passive"))
      (node (ref "R42") (pin "1") (pinfunction "1_1") (pintype "passive"))
      (node (ref "R43") (pin "1") (pinfunction "1_1") (pintype "passive"))
      (node (ref "R44") (pin "1") (pinfunction "1_1") (pintype "passive"))
      (node (ref "R45") (pin "1") (pinfunction "1_1") (pintype "passive"))
      (node (ref "R46") (pin "1") (pinfunction "1_1") (pintype "passive"))
      (node (ref "R47") (pin "1") (pinfunction "1_1") (pintype "passive"))
      (node (ref "R48") (pin "1") (pinfunction "1_1") (pintype "passive"))
      (node (ref "R49") (pin "1") (pinfunction "1_1") (pintype "passive"))
      (node (ref "R5") (pin "1") (pinfunction "1_1") (pintype "passive"))
      (node (ref "R50") (pin "1") (pinfunction "1_1") (pintype "passive"))
      (node (ref "R51") (pin "1") (pinfunction "1_1") (pintype "passive"))
      (node (ref "R52") (pin "1") (pinfunction "1_1") (pintype "passive"))
      (node (ref "R53") (pin "1") (pinfunction "1_1") (pintype "passive"))
      (node (ref "R54") (pin "1") (pinfunction "1_1") (pintype "passive"))
      (node (ref "R55") (pin "1") (pinfunction "1_1") (pintype "passive"))
      (node (ref "R56") (pin "1") (pinfunction "1_1") (pintype "passive"))
      (node (ref "R57") (pin "1") (pinfunction "1_1") (pintype "passive"))
      (node (ref "R58") (pin "1") (pinfunction "1_1") (pintype "passive"))
      (node (ref "R59") (pin "1") (pinfunction "1_1") (pintype "passive"))
      (node (ref "R6") (pin "1") (pinfunction "1_1") (pintype "passive"))
      (node (ref "R60") (pin "1") (pinfunction "1_1") (pintype "passive"))
      (node (ref "R61") (pin "1") (pinfunction "1_1") (pintype "passive"))
      (node (ref "R62") (pin "1") (pinfunction "1_1") (pintype "passive"))
      (node (ref "R63") (pin "1") (pinfunction "1_1") (pintype "passive"))
      (node (ref "R64") (pin "1") (pinfunction "1_1") (pintype "passive"))
      (node (ref "R65") (pin "1") (pinfunction "1_1") (pintype "passive"))
      (node (ref "R66") (pin "1") (pinfunction "1_1") (pintype "passive"))
      (node (ref "R67") (pin "1") (pinfunction "1_1") (pintype "passive"))
      (node (ref "R68") (pin "1") (pinfunction "1_1") (pintype "passive"))
      (node (ref "R69") (pin "1") (pinfunction "1_1") (pintype "passive"))
      (node (ref "R7") (pin "1") (pinfunction "1_1") (pintype "passive"))
      (node (ref "R70") (pin "1") (pinfunction "1_1") (pintype "passive"))
      (node (ref "R71") (pin "1") (pinfunction "1_1") (pintype "passive"))
      (node (ref "R72") (pin "1") (pinfunction "1_1") (pintype "passive"))
      (node (ref "R73") (pin "1") (pinfunction "1_1") (pintype "passive"))
      (node (ref "R74") (pin "1") (pinfunction "1_1") (pintype "passive"))
      (node (ref "R75") (pin "1") (pinfunction "1_1") (pintype "passive"))
      (node (ref "R8") (pin "1") (pinfunction "1_1") (pintype "passive"))
      (node (ref "R9") (pin "1") (pinfunction "1_1") (pintype "passive"))
    )
    (net (code "2") (name "Net-(1-Pad1)") (class "Default")
      (node (ref "1") (pin "1") (pinfunction "1_1") (pintype "passive"))
      (node (ref "R1") (pin "2") (pinfunction "2_2") (pintype "passive"))
    )
    (net (code "3") (name "Net-(2-Pad1)") (class "Default")
      (node (ref "2") (pin "1") (pinfunction "1_1") (pintype "passive"))
      (node (ref "R2") (pin "2") (pinfunction "2_2") (pintype "passive"))
    )
    (net (code "4") (name "Net-(3-Pad1)") (class "Default")
      (node (ref "3") (pin "1") (pinfunction "1_1") (pintype "passive"))
      (node (ref "R3") (pin "2") (pinfunction "2_2") (pintype "passive"))
    )
    (net (code "5") (name "Net-(4-Pad1)") (class "Default")
      (node (ref "4") (pin "1") (pinfunction "1_1") (pintype "passive"))
      (node (ref "R4") (pin "2") (pinfunction "2_2") (pintype "passive"))
    )
    (net (code "6") (name "Net-(5-Pad1)") (class "Default")
      (node (ref "5") (pin "1") (pinfunction "1_1") (pintype "passive"))
      (node (ref "R5") (pin "2") (pinfunction "2_2") (pintype "passive"))
    )
    (net (code "7") (name "Net-(6-Pad1)") (class "Default")
      (node (ref "6") (pin "1") (pinfunction "1_1") (pintype "passive"))
      (node (ref "R6") (pin "2") (pinfunction "2_2") (pintype "passive"))
    )
    (net (code "8") (name "Net-(7-Pad1)") (class "Default")
      (node (ref "7") (pin "1") (pinfunction "1_1") (pintype "passive"))
      (node (ref "R7") (pin "2") (pinfunction "2_2") (pintype "passive"))
    )
    (net (code "9") (name "Net-(8-Pad1)") (class "Default")
      (node (ref "8") (pin "1") (pinfunction "1_1") (pintype "passive"))
      (node (ref "R8") (pin "2") (pinfunction "2_2") (pintype "passive"))
    )
    (net (code "10") (name "Net-(9-Pad1)") (class "Default")
      (node (ref "9") (pin "1") (pinfunction "1_1") (pintype "passive"))
      (node (ref "R9") (pin "2") (pinfunction "2_2") (pintype "passive"))
    )
    (net (code "11") (name "Net-(10-Pad1)") (class "Default")
      (node (ref "10") (pin "1") (pinfunction "1_1") (pintype "passive"))
      (node (ref "R10") (pin "2") (pinfunction "2_2") (pintype "passive"))
    )
    (net (code "12") (name "Net-(11-Pad1)") (class "Default")
      (node (ref "11") (pin "1") (pinfunction "1_1") (pintype "passive"))
      (node (ref "R11") (pin "2") (pinfunction "2_2") (pintype "passive"))
    )
    (net (code "13") (name "Net-(12-Pad1)") (class "Default")
      (node (ref "12") (pin "1") (pinfunction "1_1") (pintype "passive"))
      (node (ref "R12") (pin "2") (pinfunction "2_2") (pintype "passive"))
    )
    (net (code "14") (name "Net-(13-Pad1)") (class "Default")
      (node (ref "13") (pin "1") (pinfunction "1_1") (pintype "passive"))
      (node (ref "R13") (pin "2") (pinfunction "2_2") (pintype "passive"))
    )
    (net (code "15") (name "Net-(14-Pad1)") (class "Default")
      (node (ref "14") (pin "1") (pinfunction "1_1") (pintype "passive"))
      (node (ref "R14") (pin "2") (pinfunction "2_2") (pintype "passive"))
    )
    (net (code "16") (name "Net-(15-Pad1)") (class "Default")
      (node (ref "15") (pin "1") (pinfunction "1_1") (pintype "passive"))
      (node (ref "R15") (pin "2") (pinfunction "2_2") (pintype "passive"))
    )
    (net (code "17") (name "Net-(16-Pad1)") (class "Default")
      (node (ref "16") (pin "1") (pinfunction "1_1") (pintype "passive"))
      (node (ref "R16") (pin "2") (pinfunction "2_2") (pintype "passive"))
    )
    (net (code "18") (name "Net-(17-Pad1)") (class "Default")
      (node (ref "17") (pin "1") (pinfunction "1_1") (pintype "passive"))
      (node (ref "R17") (pin "2") (pinfunction "2_2") (pintype "passive"))
    )
    (net (code "19") (name "Net-(18-Pad1)") (class "Default")
      (node (ref "18") (pin "1") (pinfunction "1_1") (pintype "passive"))
      (node (ref "R18") (pin "2") (pinfunction "2_2") (pintype "passive"))
    )
    (net (code "20") (name "Net-(19-Pad1)") (class "Default")
      (node (ref "19") (pin "1") (pinfunction "1_1") (pintype "passive"))
      (node (ref "R19") (pin "2") (pinfunction "2_2") (pintype "passive"))
    )
    (net (code "21") (name "Net-(20-Pad1)") (class "Default")
      (node (ref "20") (pin "1") (pinfunction "1_1") (pintype "passive"))
      (node (ref "R20") (pin "2") (pinfunction "2_2") (pintype "passive"))
    )
    (net (code "22") (name "Net-(21-Pad1)") (class "Default")
      (node (ref "21") (pin "1") (pinfunction "1_1") (pintype "passive"))
      (node (ref "R21") (pin "2") (pinfunction "2_2") (pintype "passive"))
    )
    (net (code "23") (name "Net-(22-Pad1)") (class "Default")
      (node (ref "22") (pin "1") (pinfunction "1_1") (pintype "passive"))
      (node (ref "R22") (pin "2") (pinfunction "2_2") (pintype "passive"))
    )
    (net (code "24") (name "Net-(23-Pad1)") (class "Default")
      (node (ref "23") (pin "1") (pinfunction "1_1") (pintype "passive"))
      (node (ref "R23") (pin "2") (pinfunction "2_2") (pintype "passive"))
    )
    (net (code "25") (name "Net-(24-Pad1)") (class "Default")
      (node (ref "24") (pin "1") (pinfunction "1_1") (pintype "passive"))
      (node (ref "R24") (pin "2") (pinfunction "2_2") (pintype "passive"))
    )
    (net (code "26") (name "Net-(25-Pad1)") (class "Default")
      (node (ref "25") (pin "1") (pinfunction "1_1") (pintype "passive"))
      (node (ref "R25") (pin "2") (pinfunction "2_2") (pintype "passive"))
    )
    (net (code "27") (name "Net-(26-Pad1)") (class "Default")
      (node (ref "26") (pin "1") (pinfunction "1_1") (pintype "passive"))
      (node (ref "R26") (pin "2") (pinfunction "2_2") (pintype "passive"))
    )
    (net (code "28") (name "Net-(27-Pad1)") (class "Default")
      (node (ref "27") (pin "1") (pinfunction "1_1") (pintype "passive"))
      (node (ref "R27") (pin "2") (pinfunction "2_2") (pintype "passive"))
    )
    (net (code "29") (name "Net-(28-Pad1)") (class "Default")
      (node (ref "28") (pin "1") (pinfunction "1_1") (pintype "passive"))
      (node (ref "R28") (pin "2") (pinfunction "2_2") (pintype "passive"))
    )
    (net (code "30") (name "Net-(29-Pad1)") (class "Default")
      (node (ref "29") (pin "1") (pinfunction "1_1") (pintype "passive"))
      (node (ref "R29") (pin "2") (pinfunction "2_2") (pintype "passive"))
    )
    (net (code "31") (name "Net-(30-Pad1)") (class "Default")
      (node (ref "30") (pin "1") (pinfunction "1_1") (pintype "passive"))
      (node (ref "R30") (pin "2") (pinfunction "2_2") (pintype "passive"))
    )
    (net (code "32") (name "Net-(31-Pad1)") (class "Default")
      (node (ref "31") (pin "1") (pinfunction "1_1") (pintype "passive"))
      (node (ref "R31") (pin "2") (pinfunction "2_2") (pintype "passive"))
    )
    (net (code "33") (name "Net-(32-Pad1)") (class "Default")
      (node (ref "32") (pin "1") (pinfunction "1_1") (pintype "passive"))
      (node (ref "R32") (pin "2") (pinfunction "2_2") (pintype "passive"))
    )
    (net (code "34") (name "Net-(33-Pad1)") (class "Default")
      (node (ref "33") (pin "1") (pinfunction "1_1") (pintype "passive"))
      (node (ref "R33") (pin "2") (pinfunction "2_2") (pintype "passive"))
    )
    (net (code "35") (name "Net-(34-Pad1)") (class "Default")
      (node (ref "34") (pin "1") (pinfunction "1_1") (pintype "passive"))
      (node (ref "R34") (pin "2") (pinfunction "2_2") (pintype "passive"))
    )
    (net (code "36") (name "Net-(35-Pad1)") (class "Default")
      (node (ref "35") (pin "1") (pinfunction "1_1") (pintype "passive"))
      (node (ref "R35") (pin "2") (pinfunction "2_2") (pintype "passive"))
    )
    (net (code "37") (name "Net-(36-Pad1)") (class "Default")
      (node (ref "36") (pin "1") (pinfunction "1_1") (pintype "passive"))
      (node (ref "R36") (pin "2") (pinfunction "2_2") (pintype "passive"))
    )
    (net (code "38") (name "Net-(37-Pad1)") (class "Default")
      (node (ref "37") (pin "1") (pinfunction "1_1") (pintype "passive"))
      (node (ref "R37") (pin "2") (pinfunction "2_2") (pintype "passive"))
    )
    (net (code "39") (name "Net-(38-Pad1)") (class "Default")
      (node (ref "38") (pin "1") (pinfunction "1_1") (pintype "passive"))
      (node (ref "R38") (pin "2") (pinfunction "2_2") (pintype "passive"))
    )
    (net (code "40") (name "Net-(39-Pad1)") (class "Default")
      (node (ref "39") (pin "1") (pinfunction "1_1") (pintype "passive"))
      (node (ref "R39") (pin "2") (pinfunction "2_2") (pintype "passive"))
    )
    (net (code "41") (name "Net-(40-Pad1)") (class "Default")
      (node (ref "40") (pin "1") (pinfunction "1_1") (pintype "passive"))
      (node (ref "R40") (pin "2") (pinfunction "2_2") (pintype "passive"))
    )
    (net (code "42") (name "Net-(41-Pad1)") (class "Default")
      (node (ref "41") (pin "1") (pinfunction "1_1") (pintype "passive"))
      (node (ref "R41") (pin "2") (pinfunction "2_2") (pintype "passive"))
    )
    (net (code "43") (name "Net-(42-Pad1)") (class "Default")
      (node (ref "42") (pin "1") (pinfunction "1_1") (pintype "passive"))
      (node (ref "R42") (pin "2") (pinfunction "2_2") (pintype "passive"))
    )
    (net (code "44") (name "Net-(43-Pad1)") (class "Default")
      (node (ref "43") (pin "1") (pinfunction "1_1") (pintype "passive"))
      (node (ref "R43") (pin "2") (pinfunction "2_2") (pintype "passive"))
    )
    (net (code "45") (name "Net-(44-Pad1)") (class "Default")
      (node (ref "44") (pin "1") (pinfunction "1_1") (pintype "passive"))
      (node (ref "R44") (pin "2") (pinfunction "2_2") (pintype "passive"))
    )
    (net (code "46") (name "Net-(45-Pad1)") (class "Default")
      (node (ref "45") (pin "1") (pinfunction "1_1") (pintype "passive"))
      (node (ref "R45") (pin "2") (pinfunction "2_2") (pintype "passive"))
    )
    (net (code "47") (name "Net-(46-Pad1)") (class "Default")
      (node (ref "46") (pin "1") (pinfunction "1_1") (pintype "passive"))
      (node (ref "R46") (pin "2") (pinfunction "2_2") (pintype "passive"))
    )
    (net (code "48") (name "Net-(47-Pad1)") (class "Default")
      (node (ref "47") (pin "1") (pinfunction "1_1") (pintype "passive"))
      (node (ref "R47") (pin "2") (pinfunction "2_2") (pintype "passive"))
    )
    (net (code "49") (name "Net-(48-Pad1)") (class "Default")
      (node (ref "48") (pin "1") (pinfunction "1_1") (pintype "passive"))
      (node (ref "R48") (pin "2") (pinfunction "2_2") (pintype "passive"))
    )
    (net (code "50") (name "Net-(49-Pad1)") (class "Default")
      (node (ref "49") (pin "1") (pinfunction "1_1") (pintype "passive"))
      (node (ref "R49") (pin "2") (pinfunction "2_2") (pintype "passive"))
    )
    (net (code "51") (name "Net-(50-Pad1)") (class "Default")
      (node (ref "50") (pin "1") (pinfunction "1_1") (pintype "passive"))
      (node (ref "R50") (pin "2") (pinfunction "2_2") (pintype "passive"))
    )
    (net (code "52") (name "Net-(51-Pad1)") (class "Default")
      (node (ref "51") (pin "1") (pinfunction "1_1") (pintype "passive"))
      (node (ref "R51") (pin "2") (pinfunction "2_2") (pintype "passive"))
    )
    (net (code "53") (name "Net-(52-Pad1)") (class "Default")
      (node (ref "52") (pin "1") (pinfunction "1_1") (pintype "passive"))
      (node (ref "R52") (pin "2") (pinfunction "2_2") (pintype "passive"))
    )
    (net (code "54") (name "Net-(53-Pad1)") (class "Default")
      (node (ref "53") (pin "1") (pinfunction "1_1") (pintype "passive"))
      (node (ref "R53") (pin "2") (pinfunction "2_2") (pintype "passive"))
    )
    (net (code "55") (name "Net-(54-Pad1)") (class "Default")
      (node (ref "54") (pin "1") (pinfunction "1_1") (pintype "passive"))
      (node (ref "R54") (pin "2") (pinfunction "2_2") (pintype "passive"))
    )
    (net (code "56") (name "Net-(55-Pad1)") (class "Default")
      (node (ref "55") (pin "1") (pinfunction "1_1") (pintype "passive"))
      (node (ref "R55") (pin "2") (pinfunction "2_2") (pintype "passive"))
    )
    (net (code "57") (name "Net-(56-Pad1)") (class "Default")
      (node (ref "56") (pin "1") (pinfunction "1_1") (pintype "passive"))
      (node (ref "R56") (pin "2") (pinfunction "2_2") (pintype "passive"))
    )
    (net (code "58") (name "Net-(57-Pad1)") (class "Default")
      (node (ref "57") (pin "1") (pinfunction "1_1") (pintype "passive"))
      (node (ref "R57") (pin "2") (pinfunction "2_2") (pintype "passive"))
    )
    (net (code "59") (name "Net-(58-Pad1)") (class "Default")
      (node (ref "58") (pin "1") (pinfunction "1_1") (pintype "passive"))
      (node (ref "R58") (pin "2") (pinfunction "2_2") (pintype "passive"))
    )
    (net (code "60") (name "Net-(59-Pad1)") (class "Default")
      (node (ref "59") (pin "1") (pinfunction "1_1") (pintype "passive"))
      (node (ref "R59") (pin "2") (pinfunction "2_2") (pintype "passive"))
    )
    (net (code "61") (name "Net-(60-Pad1)") (class "Default")
      (node (ref "60") (pin "1") (pinfunction "1_1") (pintype "passive"))
      (node (ref "R60") (pin "2") (pinfunction "2_2") (pintype "passive"))
    )
    (net (code "62") (name "Net-(61-Pad1)") (class "Default")
      (node (ref "61") (pin "1") (pinfunction "1_1") (pintype "passive"))
      (node (ref "R61") (pin "2") (pinfunction "2_2") (pintype "passive"))
    )
    (net (code "63") (name "Net-(62-Pad1)") (class "Default")
      (node (ref "62") (pin "1") (pinfunction "1_1") (pintype "passive"))
      (node (ref "R62") (pin "2") (pinfunction "2_2") (pintype "passive"))
    )
    (net (code "64") (name "Net-(63-Pad1)") (class "Default")
      (node (ref "63") (pin "1") (pinfunction "1_1") (pintype "passive"))
      (node (ref "R63") (pin "2") (pinfunction "2_2") (pintype "passive"))
    )
    (net (code "65") (name "Net-(64-Pad1)") (class "Default")
      (node (ref "64") (pin "1") (pinfunction "1_1") (pintype "passive"))
      (node (ref "R64") (pin "2") (pinfunction "2_2") (pintype "passive"))
    )
    (net (code "66") (name "Net-(65-Pad1)") (class "Default")
      (node (ref "65") (pin "1") (pinfunction "1_1") (pintype "passive"))
      (node (ref "R65") (pin "2") (pinfunction "2_2") (pintype "passive"))
    )
    (net (code "67") (name "Net-(66-Pad1)") (class "Default")
      (node (ref "66") (pin "1") (pinfunction "1_1") (pintype "passive"))
      (node (ref "R66") (pin "2") (pinfunction "2_2") (pintype "passive"))
    )
    (net (code "68") (name "Net-(67-Pad1)") (class "Default")
      (node (ref "67") (pin "1") (pinfunction "1_1") (pintype "passive"))
      (node (ref "R67") (pin "2") (pinfunction "2_2") (pintype "passive"))
    )
    (net (code "69") (name "Net-(68-Pad1)") (class "Default")
      (node (ref "68") (pin "1") (pinfunction "1_1") (pintype "passive"))
      (node (ref "R68") (pin "2") (pinfunction "2_2") (pintype "passive"))
    )
    (net (code "70") (name "Net-(69-Pad1)") (class "Default")
      (node (ref "69") (pin "1") (pinfunction "1_1") (pintype "passive"))
      (node (ref "R69") (pin "2") (pinfunction "2_2") (pintype "passive"))
    )
    (net (code "71") (name "Net-(70-Pad1)") (class "Default")
      (node (ref "70") (pin "1") (pinfunction "1_1") (pintype "passive"))
      (node (ref "R70") (pin "2") (pinfunction "2_2") (pintype "passive"))
    )
    (net (code "72") (name "Net-(71-Pad1)") (class "Default")
      (node (ref "71") (pin "1") (pinfunction "1_1") (pintype "passive"))
      (node (ref "R71") (pin "2") (pinfunction "2_2") (pintype "passive"))
    )
    (net (code "73") (name "Net-(72-Pad1)") (class "Default")
      (node (ref "72") (pin "1") (pinfunction "1_1") (pintype "passive"))
      (node (ref "R72") (pin "2") (pinfunction "2_2") (pintype "passive"))
    )
    (net (code "74") (name "Net-(73-Pad1)") (class "Default")
      (node (ref "73") (pin "1") (pinfunction "1_1") (pintype "passive"))
      (node (ref "R73") (pin "2") (pinfunction "2_2") (pintype "passive"))
    )
    (net (code "75") (name "Net-(74-Pad1)") (class "Default")
      (node (ref "74") (pin "1") (pinfunction "1_1") (pintype "passive"))
      (node (ref "R74") (pin "2") (pinfunction "2_2") (pintype "passive"))
    )
    (net (code "76") (name "Net-(74HC595Sparkfun_1-A)") (class "Default")
      (node (ref "1") (pin "2") (pinfunction "2_2") (pintype "passive"))
      (node (ref "74HC595Sparkfun_1") (pin "15") (pinfunction "A_15") (pintype "passive"))
    )
    (net (code "77") (name "Net-(74HC595Sparkfun_1-B)") (class "Default")
      (node (ref "2") (pin "2") (pinfunction "2_2") (pintype "passive"))
      (node (ref "74HC595Sparkfun_1") (pin "16") (pinfunction "B_16") (pintype "passive"))
    )
    (net (code "78") (name "Net-(74HC595Sparkfun_1-C)") (class "Default")
      (node (ref "3") (pin "2") (pinfunction "2_2") (pintype "passive"))
      (node (ref "74HC595Sparkfun_1") (pin "17") (pinfunction "C_17") (pintype "passive"))
    )
    (net (code "79") (name "Net-(74HC595Sparkfun_1-Clock-Pad5)") (class "Default")
      (node (ref "74HC595Sparkfun_1") (pin "5") (pinfunction "Clock_5") (pintype "passive"))
      (node (ref "74HC595Sparkfun_10") (pin "5") (pinfunction "Clock_5") (pintype "passive"))
      (node (ref "74HC595Sparkfun_2") (pin "5") (pinfunction "Clock_5") (pintype "passive"))
      (node (ref "74HC595Sparkfun_3") (pin "5") (pinfunction "Clock_5") (pintype "passive"))
      (node (ref "74HC595Sparkfun_4") (pin "5") (pinfunction "Clock_5") (pintype "passive"))
      (node (ref "74HC595Sparkfun_5") (pin "5") (pinfunction "Clock_5") (pintype "passive"))
      (node (ref "74HC595Sparkfun_6") (pin "5") (pinfunction "Clock_5") (pintype "passive"))
      (node (ref "74HC595Sparkfun_7") (pin "5") (pinfunction "Clock_5") (pintype "passive"))
      (node (ref "74HC595Sparkfun_8") (pin "5") (pinfunction "Clock_5") (pintype "passive"))
      (node (ref "74HC595Sparkfun_9") (pin "5") (pinfunction "Clock_5") (pintype "passive"))
      (node (ref "Maître") (pin "D12") (pinfunction "D12_D12") (pintype "passive"))
    )
    (net (code "80") (name "Net-(74HC595Sparkfun_1-D)") (class "Default")
      (node (ref "4") (pin "2") (pinfunction "2_2") (pintype "passive"))
      (node (ref "74HC595Sparkfun_1") (pin "18") (pinfunction "D_18") (pintype "passive"))
    )
    (net (code "81") (name "Net-(74HC595Sparkfun_1-E)") (class "Default")
      (node (ref "5") (pin "2") (pinfunction "2_2") (pintype "passive"))
      (node (ref "74HC595Sparkfun_1") (pin "19") (pinfunction "E_19") (pintype "passive"))
    )
    (net (code "82") (name "Net-(74HC595Sparkfun_1-F)") (class "Default")
      (node (ref "6") (pin "2") (pinfunction "2_2") (pintype "passive"))
      (node (ref "74HC595Sparkfun_1") (pin "20") (pinfunction "F_20") (pintype "passive"))
    )
    (net (code "83") (name "Net-(74HC595Sparkfun_1-G)") (class "Default")
      (node (ref "7") (pin "2") (pinfunction "2_2") (pintype "passive"))
      (node (ref "74HC595Sparkfun_1") (pin "21") (pinfunction "G_21") (pintype "passive"))
    )
    (net (code "84") (name "Net-(74HC595Sparkfun_1-H)") (class "Default")
      (node (ref "74HC595Sparkfun_1") (pin "22") (pinfunction "H_22") (pintype "passive"))
      (node (ref "8") (pin "2") (pinfunction "2_2") (pintype "passive"))
    )
    (net (code "85") (name "Net-(74HC595Sparkfun_1-L_Clock-Pad6)") (class "Default")
      (node (ref "74HC595Sparkfun_1") (pin "6") (pinfunction "L_Clock_6") (pintype "passive"))
      (node (ref "74HC595Sparkfun_10") (pin "6") (pinfunction "L_Clock_6") (pintype "passive"))
      (node (ref "74HC595Sparkfun_2") (pin "6") (pinfunction "L_Clock_6") (pintype "passive"))
      (node (ref "74HC595Sparkfun_3") (pin "6") (pinfunction "L_Clock_6") (pintype "passive"))
      (node (ref "74HC595Sparkfun_4") (pin "6") (pinfunction "L_Clock_6") (pintype "passive"))
      (node (ref "74HC595Sparkfun_5") (pin "6") (pinfunction "L_Clock_6") (pintype "passive"))
      (node (ref "74HC595Sparkfun_6") (pin "6") (pinfunction "L_Clock_6") (pintype "passive"))
      (node (ref "74HC595Sparkfun_7") (pin "6") (pinfunction "L_Clock_6") (pintype "passive"))
      (node (ref "74HC595Sparkfun_8") (pin "6") (pinfunction "L_Clock_6") (pintype "passive"))
      (node (ref "74HC595Sparkfun_9") (pin "6") (pinfunction "L_Clock_6") (pintype "passive"))
      (node (ref "Maître") (pin "D8") (pinfunction "D8_D8") (pintype "passive"))
    )
    (net (code "86") (name "Net-(74HC595Sparkfun_1-SER_IN)") (class "Default")
      (node (ref "74HC595Sparkfun_1") (pin "7") (pinfunction "SER_IN_7") (pintype "passive"))
      (node (ref "Maître") (pin "D11") (pinfunction "*D11_D11") (pintype "passive"))
    )
    (net (code "87") (name "Net-(74HC595Sparkfun_1-SER_OUT)") (class "Default")
      (node (ref "74HC595Sparkfun_1") (pin "14") (pinfunction "SER_OUT_14") (pintype "passive"))
      (node (ref "74HC595Sparkfun_2") (pin "7") (pinfunction "SER_IN_7") (pintype "passive"))
    )
    (net (code "88") (name "Net-(74HC595Sparkfun_2-A)") (class "Default")
      (node (ref "74HC595Sparkfun_2") (pin "15") (pinfunction "A_15") (pintype "passive"))
      (node (ref "9") (pin "2") (pinfunction "2_2") (pintype "passive"))
    )
    (net (code "89") (name "Net-(74HC595Sparkfun_2-B)") (class "Default")
      (node (ref "10") (pin "2") (pinfunction "2_2") (pintype "passive"))
      (node (ref "74HC595Sparkfun_2") (pin "16") (pinfunction "B_16") (pintype "passive"))
    )
    (net (code "90") (name "Net-(74HC595Sparkfun_2-C)") (class "Default")
      (node (ref "11") (pin "2") (pinfunction "2_2") (pintype "passive"))
      (node (ref "74HC595Sparkfun_2") (pin "17") (pinfunction "C_17") (pintype "passive"))
    )
    (net (code "91") (name "Net-(74HC595Sparkfun_2-D)") (class "Default")
      (node (ref "12") (pin "2") (pinfunction "2_2") (pintype "passive"))
      (node (ref "74HC595Sparkfun_2") (pin "18") (pinfunction "D_18") (pintype "passive"))
    )
    (net (code "92") (name "Net-(74HC595Sparkfun_2-E)") (class "Default")
      (node (ref "13") (pin "2") (pinfunction "2_2") (pintype "passive"))
      (node (ref "74HC595Sparkfun_2") (pin "19") (pinfunction "E_19") (pintype "passive"))
    )
    (net (code "93") (name "Net-(74HC595Sparkfun_2-F)") (class "Default")
      (node (ref "14") (pin "2") (pinfunction "2_2") (pintype "passive"))
      (node (ref "74HC595Sparkfun_2") (pin "20") (pinfunction "F_20") (pintype "passive"))
    )
    (net (code "94") (name "Net-(74HC595Sparkfun_2-G)") (class "Default")
      (node (ref "15") (pin "2") (pinfunction "2_2") (pintype "passive"))
      (node (ref "74HC595Sparkfun_2") (pin "21") (pinfunction "G_21") (pintype "passive"))
    )
    (net (code "95") (name "Net-(74HC595Sparkfun_2-H)") (class "Default")
      (node (ref "16") (pin "2") (pinfunction "2_2") (pintype "passive"))
      (node (ref "74HC595Sparkfun_2") (pin "22") (pinfunction "H_22") (pintype "passive"))
    )
    (net (code "96") (name "Net-(74HC595Sparkfun_2-SER_OUT)") (class "Default")
      (node (ref "74HC595Sparkfun_2") (pin "14") (pinfunction "SER_OUT_14") (pintype "passive"))
      (node (ref "74HC595Sparkfun_3") (pin "7") (pinfunction "SER_IN_7") (pintype "passive"))
    )
    (net (code "97") (name "Net-(74HC595Sparkfun_3-A)") (class "Default")
      (node (ref "17") (pin "2") (pinfunction "2_2") (pintype "passive"))
      (node (ref "74HC595Sparkfun_3") (pin "15") (pinfunction "A_15") (pintype "passive"))
    )
    (net (code "98") (name "Net-(74HC595Sparkfun_3-B)") (class "Default")
      (node (ref "18") (pin "2") (pinfunction "2_2") (pintype "passive"))
      (node (ref "74HC595Sparkfun_3") (pin "16") (pinfunction "B_16") (pintype "passive"))
    )
    (net (code "99") (name "Net-(74HC595Sparkfun_3-C)") (class "Default")
      (node (ref "19") (pin "2") (pinfunction "2_2") (pintype "passive"))
      (node (ref "74HC595Sparkfun_3") (pin "17") (pinfunction "C_17") (pintype "passive"))
    )
    (net (code "100") (name "Net-(74HC595Sparkfun_3-D)") (class "Default")
      (node (ref "20") (pin "2") (pinfunction "2_2") (pintype "passive"))
      (node (ref "74HC595Sparkfun_3") (pin "18") (pinfunction "D_18") (pintype "passive"))
    )
    (net (code "101") (name "Net-(74HC595Sparkfun_3-E)") (class "Default")
      (node (ref "21") (pin "2") (pinfunction "2_2") (pintype "passive"))
      (node (ref "74HC595Sparkfun_3") (pin "19") (pinfunction "E_19") (pintype "passive"))
    )
    (net (code "102") (name "Net-(74HC595Sparkfun_3-F)") (class "Default")
      (node (ref "22") (pin "2") (pinfunction "2_2") (pintype "passive"))
      (node (ref "74HC595Sparkfun_3") (pin "20") (pinfunction "F_20") (pintype "passive"))
    )
    (net (code "103") (name "Net-(74HC595Sparkfun_3-G)") (class "Default")
      (node (ref "23") (pin "2") (pinfunction "2_2") (pintype "passive"))
      (node (ref "74HC595Sparkfun_3") (pin "21") (pinfunction "G_21") (pintype "passive"))
    )
    (net (code "104") (name "Net-(74HC595Sparkfun_3-H)") (class "Default")
      (node (ref "24") (pin "2") (pinfunction "2_2") (pintype "passive"))
      (node (ref "74HC595Sparkfun_3") (pin "22") (pinfunction "H_22") (pintype "passive"))
    )
    (net (code "105") (name "Net-(74HC595Sparkfun_3-SER_OUT)") (class "Default")
      (node (ref "74HC595Sparkfun_3") (pin "14") (pinfunction "SER_OUT_14") (pintype "passive"))
      (node (ref "74HC595Sparkfun_4") (pin "7") (pinfunction "SER_IN_7") (pintype "passive"))
    )
    (net (code "106") (name "Net-(74HC595Sparkfun_4-A)") (class "Default")
      (node (ref "25") (pin "2") (pinfunction "2_2") (pintype "passive"))
      (node (ref "74HC595Sparkfun_4") (pin "15") (pinfunction "A_15") (pintype "passive"))
    )
    (net (code "107") (name "Net-(74HC595Sparkfun_4-B)") (class "Default")
      (node (ref "26") (pin "2") (pinfunction "2_2") (pintype "passive"))
      (node (ref "74HC595Sparkfun_4") (pin "16") (pinfunction "B_16") (pintype "passive"))
    )
    (net (code "108") (name "Net-(74HC595Sparkfun_4-C)") (class "Default")
      (node (ref "27") (pin "2") (pinfunction "2_2") (pintype "passive"))
      (node (ref "74HC595Sparkfun_4") (pin "17") (pinfunction "C_17") (pintype "passive"))
    )
    (net (code "109") (name "Net-(74HC595Sparkfun_4-D)") (class "Default")
      (node (ref "28") (pin "2") (pinfunction "2_2") (pintype "passive"))
      (node (ref "74HC595Sparkfun_4") (pin "18") (pinfunction "D_18") (pintype "passive"))
    )
    (net (code "110") (name "Net-(74HC595Sparkfun_4-E)") (class "Default")
      (node (ref "29") (pin "2") (pinfunction "2_2") (pintype "passive"))
      (node (ref "74HC595Sparkfun_4") (pin "19") (pinfunction "E_19") (pintype "passive"))
    )
    (net (code "111") (name "Net-(74HC595Sparkfun_4-F)") (class "Default")
      (node (ref "30") (pin "2") (pinfunction "2_2") (pintype "passive"))
      (node (ref "74HC595Sparkfun_4") (pin "20") (pinfunction "F_20") (pintype "passive"))
    )
    (net (code "112") (name "Net-(74HC595Sparkfun_4-G)") (class "Default")
      (node (ref "31") (pin "2") (pinfunction "2_2") (pintype "passive"))
      (node (ref "74HC595Sparkfun_4") (pin "21") (pinfunction "G_21") (pintype "passive"))
    )
    (net (code "113") (name "Net-(74HC595Sparkfun_4-H)") (class "Default")
      (node (ref "32") (pin "2") (pinfunction "2_2") (pintype "passive"))
      (node (ref "74HC595Sparkfun_4") (pin "22") (pinfunction "H_22") (pintype "passive"))
    )
    (net (code "114") (name "Net-(74HC595Sparkfun_4-SER_OUT)") (class "Default")
      (node (ref "74HC595Sparkfun_4") (pin "14") (pinfunction "SER_OUT_14") (pintype "passive"))
      (node (ref "74HC595Sparkfun_5") (pin "7") (pinfunction "SER_IN_7") (pintype "passive"))
    )
    (net (code "115") (name "Net-(74HC595Sparkfun_5-A)") (class "Default")
      (node (ref "33") (pin "2") (pinfunction "2_2") (pintype "passive"))
      (node (ref "74HC595Sparkfun_5") (pin "15") (pinfunction "A_15") (pintype "passive"))
    )
    (net (code "116") (name "Net-(74HC595Sparkfun_5-B)") (class "Default")
      (node (ref "34") (pin "2") (pinfunction "2_2") (pintype "passive"))
      (node (ref "74HC595Sparkfun_5") (pin "16") (pinfunction "B_16") (pintype "passive"))
    )
    (net (code "117") (name "Net-(74HC595Sparkfun_5-C)") (class "Default")
      (node (ref "35") (pin "2") (pinfunction "2_2") (pintype "passive"))
      (node (ref "74HC595Sparkfun_5") (pin "17") (pinfunction "C_17") (pintype "passive"))
    )
    (net (code "118") (name "Net-(74HC595Sparkfun_5-D)") (class "Default")
      (node (ref "36") (pin "2") (pinfunction "2_2") (pintype "passive"))
      (node (ref "74HC595Sparkfun_5") (pin "18") (pinfunction "D_18") (pintype "passive"))
    )
    (net (code "119") (name "Net-(74HC595Sparkfun_5-E)") (class "Default")
      (node (ref "37") (pin "2") (pinfunction "2_2") (pintype "passive"))
      (node (ref "74HC595Sparkfun_5") (pin "19") (pinfunction "E_19") (pintype "passive"))
    )
    (net (code "120") (name "Net-(74HC595Sparkfun_5-F)") (class "Default")
      (node (ref "38") (pin "2") (pinfunction "2_2") (pintype "passive"))
      (node (ref "74HC595Sparkfun_5") (pin "20") (pinfunction "F_20") (pintype "passive"))
    )
    (net (code "121") (name "Net-(74HC595Sparkfun_5-G)") (class "Default")
      (node (ref "39") (pin "2") (pinfunction "2_2") (pintype "passive"))
      (node (ref "74HC595Sparkfun_5") (pin "21") (pinfunction "G_21") (pintype "passive"))
    )
    (net (code "122") (name "Net-(74HC595Sparkfun_5-H)") (class "Default")
      (node (ref "40") (pin "2") (pinfunction "2_2") (pintype "passive"))
      (node (ref "74HC595Sparkfun_5") (pin "22") (pinfunction "H_22") (pintype "passive"))
    )
    (net (code "123") (name "Net-(74HC595Sparkfun_5-SER_OUT)") (class "Default")
      (node (ref "74HC595Sparkfun_5") (pin "14") (pinfunction "SER_OUT_14") (pintype "passive"))
      (node (ref "74HC595Sparkfun_6") (pin "7") (pinfunction "SER_IN_7") (pintype "passive"))
    )
    (net (code "124") (name "Net-(74HC595Sparkfun_6-A)") (class "Default")
      (node (ref "41") (pin "2") (pinfunction "2_2") (pintype "passive"))
      (node (ref "74HC595Sparkfun_6") (pin "15") (pinfunction "A_15") (pintype "passive"))
    )
    (net (code "125") (name "Net-(74HC595Sparkfun_6-B)") (class "Default")
      (node (ref "42") (pin "2") (pinfunction "2_2") (pintype "passive"))
      (node (ref "74HC595Sparkfun_6") (pin "16") (pinfunction "B_16") (pintype "passive"))
    )
    (net (code "126") (name "Net-(74HC595Sparkfun_6-C)") (class "Default")
      (node (ref "43") (pin "2") (pinfunction "2_2") (pintype "passive"))
      (node (ref "74HC595Sparkfun_6") (pin "17") (pinfunction "C_17") (pintype "passive"))
    )
    (net (code "127") (name "Net-(74HC595Sparkfun_6-D)") (class "Default")
      (node (ref "44") (pin "2") (pinfunction "2_2") (pintype "passive"))
      (node (ref "74HC595Sparkfun_6") (pin "18") (pinfunction "D_18") (pintype "passive"))
    )
    (net (code "128") (name "Net-(74HC595Sparkfun_6-E)") (class "Default")
      (node (ref "45") (pin "2") (pinfunction "2_2") (pintype "passive"))
      (node (ref "74HC595Sparkfun_6") (pin "19") (pinfunction "E_19") (pintype "passive"))
    )
    (net (code "129") (name "Net-(74HC595Sparkfun_6-F)") (class "Default")
      (node (ref "46") (pin "2") (pinfunction "2_2") (pintype "passive"))
      (node (ref "74HC595Sparkfun_6") (pin "20") (pinfunction "F_20") (pintype "passive"))
    )
    (net (code "130") (name "Net-(74HC595Sparkfun_6-G)") (class "Default")
      (node (ref "47") (pin "2") (pinfunction "2_2") (pintype "passive"))
      (node (ref "74HC595Sparkfun_6") (pin "21") (pinfunction "G_21") (pintype "passive"))
    )
    (net (code "131") (name "Net-(74HC595Sparkfun_6-H)") (class "Default")
      (node (ref "48") (pin "2") (pinfunction "2_2") (pintype "passive"))
      (node (ref "74HC595Sparkfun_6") (pin "22") (pinfunction "H_22") (pintype "passive"))
    )
    (net (code "132") (name "Net-(74HC595Sparkfun_6-SER_OUT)") (class "Default")
      (node (ref "74HC595Sparkfun_6") (pin "14") (pinfunction "SER_OUT_14") (pintype "passive"))
      (node (ref "74HC595Sparkfun_7") (pin "7") (pinfunction "SER_IN_7") (pintype "passive"))
    )
    (net (code "133") (name "Net-(74HC595Sparkfun_7-A)") (class "Default")
      (node (ref "49") (pin "2") (pinfunction "2_2") (pintype "passive"))
      (node (ref "74HC595Sparkfun_7") (pin "15") (pinfunction "A_15") (pintype "passive"))
    )
    (net (code "134") (name "Net-(74HC595Sparkfun_7-B)") (class "Default")
      (node (ref "50") (pin "2") (pinfunction "2_2") (pintype "passive"))
      (node (ref "74HC595Sparkfun_7") (pin "16") (pinfunction "B_16") (pintype "passive"))
    )
    (net (code "135") (name "Net-(74HC595Sparkfun_7-C)") (class "Default")
      (node (ref "51") (pin "2") (pinfunction "2_2") (pintype "passive"))
      (node (ref "74HC595Sparkfun_7") (pin "17") (pinfunction "C_17") (pintype "passive"))
    )
    (net (code "136") (name "Net-(74HC595Sparkfun_7-D)") (class "Default")
      (node (ref "52") (pin "2") (pinfunction "2_2") (pintype "passive"))
      (node (ref "74HC595Sparkfun_7") (pin "18") (pinfunction "D_18") (pintype "passive"))
    )
    (net (code "137") (name "Net-(74HC595Sparkfun_7-E)") (class "Default")
      (node (ref "53") (pin "2") (pinfunction "2_2") (pintype "passive"))
      (node (ref "74HC595Sparkfun_7") (pin "19") (pinfunction "E_19") (pintype "passive"))
    )
    (net (code "138") (name "Net-(74HC595Sparkfun_7-F)") (class "Default")
      (node (ref "54") (pin "2") (pinfunction "2_2") (pintype "passive"))
      (node (ref "74HC595Sparkfun_7") (pin "20") (pinfunction "F_20") (pintype "passive"))
    )
    (net (code "139") (name "Net-(74HC595Sparkfun_7-G)") (class "Default")
      (node (ref "55") (pin "2") (pinfunction "2_2") (pintype "passive"))
      (node (ref "74HC595Sparkfun_7") (pin "21") (pinfunction "G_21") (pintype "passive"))
    )
    (net (code "140") (name "Net-(74HC595Sparkfun_7-H)") (class "Default")
      (node (ref "56") (pin "2") (pinfunction "2_2") (pintype "passive"))
      (node (ref "74HC595Sparkfun_7") (pin "22") (pinfunction "H_22") (pintype "passive"))
    )
    (net (code "141") (name "Net-(74HC595Sparkfun_7-SER_OUT)") (class "Default")
      (node (ref "74HC595Sparkfun_7") (pin "14") (pinfunction "SER_OUT_14") (pintype "passive"))
      (node (ref "74HC595Sparkfun_8") (pin "7") (pinfunction "SER_IN_7") (pintype "passive"))
    )
    (net (code "142") (name "Net-(74HC595Sparkfun_8-A)") (class "Default")
      (node (ref "57") (pin "2") (pinfunction "2_2") (pintype "passive"))
      (node (ref "74HC595Sparkfun_8") (pin "15") (pinfunction "A_15") (pintype "passive"))
    )
    (net (code "143") (name "Net-(74HC595Sparkfun_8-B)") (class "Default")
      (node (ref "58") (pin "2") (pinfunction "2_2") (pintype "passive"))
      (node (ref "74HC595Sparkfun_8") (pin "16") (pinfunction "B_16") (pintype "passive"))
    )
    (net (code "144") (name "Net-(74HC595Sparkfun_8-C)") (class "Default")
      (node (ref "59") (pin "2") (pinfunction "2_2") (pintype "passive"))
      (node (ref "74HC595Sparkfun_8") (pin "17") (pinfunction "C_17") (pintype "passive"))
    )
    (net (code "145") (name "Net-(74HC595Sparkfun_8-D)") (class "Default")
      (node (ref "60") (pin "2") (pinfunction "2_2") (pintype "passive"))
      (node (ref "74HC595Sparkfun_8") (pin "18") (pinfunction "D_18") (pintype "passive"))
    )
    (net (code "146") (name "Net-(74HC595Sparkfun_8-E)") (class "Default")
      (node (ref "61") (pin "2") (pinfunction "2_2") (pintype "passive"))
      (node (ref "74HC595Sparkfun_8") (pin "19") (pinfunction "E_19") (pintype "passive"))
    )
    (net (code "147") (name "Net-(74HC595Sparkfun_8-F)") (class "Default")
      (node (ref "62") (pin "2") (pinfunction "2_2") (pintype "passive"))
      (node (ref "74HC595Sparkfun_8") (pin "20") (pinfunction "F_20") (pintype "passive"))
    )
    (net (code "148") (name "Net-(74HC595Sparkfun_8-G)") (class "Default")
      (node (ref "63") (pin "2") (pinfunction "2_2") (pintype "passive"))
      (node (ref "74HC595Sparkfun_8") (pin "21") (pinfunction "G_21") (pintype "passive"))
    )
    (net (code "149") (name "Net-(74HC595Sparkfun_8-H)") (class "Default")
      (node (ref "64") (pin "2") (pinfunction "2_2") (pintype "passive"))
      (node (ref "74HC595Sparkfun_8") (pin "22") (pinfunction "H_22") (pintype "passive"))
    )
    (net (code "150") (name "Net-(74HC595Sparkfun_8-SER_OUT)") (class "Default")
      (node (ref "74HC595Sparkfun_8") (pin "14") (pinfunction "SER_OUT_14") (pintype "passive"))
      (node (ref "74HC595Sparkfun_9") (pin "7") (pinfunction "SER_IN_7") (pintype "passive"))
    )
    (net (code "151") (name "Net-(74HC595Sparkfun_9-A)") (class "Default")
      (node (ref "65") (pin "2") (pinfunction "2_2") (pintype "passive"))
      (node (ref "74HC595Sparkfun_9") (pin "15") (pinfunction "A_15") (pintype "passive"))
    )
    (net (code "152") (name "Net-(74HC595Sparkfun_9-B)") (class "Default")
      (node (ref "66") (pin "2") (pinfunction "2_2") (pintype "passive"))
      (node (ref "74HC595Sparkfun_9") (pin "16") (pinfunction "B_16") (pintype "passive"))
    )
    (net (code "153") (name "Net-(74HC595Sparkfun_9-C)") (class "Default")
      (node (ref "67") (pin "2") (pinfunction "2_2") (pintype "passive"))
      (node (ref "74HC595Sparkfun_9") (pin "17") (pinfunction "C_17") (pintype "passive"))
    )
    (net (code "154") (name "Net-(74HC595Sparkfun_9-D)") (class "Default")
      (node (ref "68") (pin "2") (pinfunction "2_2") (pintype "passive"))
      (node (ref "74HC595Sparkfun_9") (pin "18") (pinfunction "D_18") (pintype "passive"))
    )
    (net (code "155") (name "Net-(74HC595Sparkfun_9-E)") (class "Default")
      (node (ref "69") (pin "2") (pinfunction "2_2") (pintype "passive"))
      (node (ref "74HC595Sparkfun_9") (pin "19") (pinfunction "E_19") (pintype "passive"))
    )
    (net (code "156") (name "Net-(74HC595Sparkfun_9-F)") (class "Default")
      (node (ref "70") (pin "2") (pinfunction "2_2") (pintype "passive"))
      (node (ref "74HC595Sparkfun_9") (pin "20") (pinfunction "F_20") (pintype "passive"))
    )
    (net (code "157") (name "Net-(74HC595Sparkfun_9-G)") (class "Default")
      (node (ref "71") (pin "2") (pinfunction "2_2") (pintype "passive"))
      (node (ref "74HC595Sparkfun_9") (pin "21") (pinfunction "G_21") (pintype "passive"))
    )
    (net (code "158") (name "Net-(74HC595Sparkfun_9-H)") (class "Default")
      (node (ref "72") (pin "2") (pinfunction "2_2") (pintype "passive"))
      (node (ref "74HC595Sparkfun_9") (pin "22") (pinfunction "H_22") (pintype "passive"))
    )
    (net (code "159") (name "Net-(74HC595Sparkfun_10-A)") (class "Default")
      (node (ref "73") (pin "2") (pinfunction "2_2") (pintype "passive"))
      (node (ref "74HC595Sparkfun_10") (pin "15") (pinfunction "A_15") (pintype "passive"))
    )
    (net (code "160") (name "Net-(74HC595Sparkfun_10-B)") (class "Default")
      (node (ref "74") (pin "2") (pinfunction "2_2") (pintype "passive"))
      (node (ref "74HC595Sparkfun_10") (pin "16") (pinfunction "B_16") (pintype "passive"))
    )
    (net (code "161") (name "Net-(74HC595Sparkfun_10-C)") (class "Default")
      (node (ref "74HC595Sparkfun_10") (pin "17") (pinfunction "C_17") (pintype "passive"))
      (node (ref "75") (pin "2") (pinfunction "2_2") (pintype "passive"))
    )
    (net (code "162") (name "Net-(74HC595Sparkfun_10-SER_IN)") (class "Default")
      (node (ref "74HC595Sparkfun_10") (pin "7") (pinfunction "SER_IN_7") (pintype "passive"))
      (node (ref "74HC595Sparkfun_9") (pin "14") (pinfunction "SER_OUT_14") (pintype "passive"))
    )
    (net (code "163") (name "Net-(75-Pad1)") (class "Default")
      (node (ref "75") (pin "1") (pinfunction "1_1") (pintype "passive"))
      (node (ref "R75") (pin "2") (pinfunction "2_2") (pintype "passive"))
    )
    (net (code "164") (name "Net-(Esclave 1-Pad1)") (class "Default")
      (node (ref "Esclave 1") (pin "1") (pinfunction "1_1") (pintype "passive"))
      (node (ref "Esclave 2") (pin "1") (pinfunction "1_1") (pintype "passive"))
      (node (ref "Esclave 3") (pin "1") (pinfunction "1_1") (pintype "passive"))
      (node (ref "Maître") (pin "A5") (pinfunction "A5_A5") (pintype "passive"))
    )
    (net (code "165") (name "Net-(Esclave 1-Pad2)") (class "Default")
      (node (ref "Esclave 1") (pin "2") (pinfunction "2_2") (pintype "passive"))
      (node (ref "Esclave 2") (pin "2") (pinfunction "2_2") (pintype "passive"))
      (node (ref "Esclave 3") (pin "2") (pinfunction "2_2") (pintype "passive"))
      (node (ref "Maître") (pin "A4") (pinfunction "A4_A4") (pintype "passive"))
    )
    (net (code "166") (name "VCC") (class "Default")
      (node (ref "74HC595Sparkfun_1") (pin "1") (pinfunction "VCC_1") (pintype "passive"))
      (node (ref "74HC595Sparkfun_1") (pin "3") (pinfunction "/Reset_3") (pintype "passive"))
      (node (ref "74HC595Sparkfun_10") (pin "1") (pinfunction "VCC_1") (pintype "passive"))
      (node (ref "74HC595Sparkfun_10") (pin "3") (pinfunction "/Reset_3") (pintype "passive"))
      (node (ref "74HC595Sparkfun_2") (pin "1") (pinfunction "VCC_1") (pintype "passive"))
      (node (ref "74HC595Sparkfun_2") (pin "3") (pinfunction "/Reset_3") (pintype "passive"))
      (node (ref "74HC595Sparkfun_3") (pin "1") (pinfunction "VCC_1") (pintype "passive"))
      (node (ref "74HC595Sparkfun_3") (pin "3") (pinfunction "/Reset_3") (pintype "passive"))
      (node (ref "74HC595Sparkfun_4") (pin "1") (pinfunction "VCC_1") (pintype "passive"))
      (node (ref "74HC595Sparkfun_4") (pin "3") (pinfunction "/Reset_3") (pintype "passive"))
      (node (ref "74HC595Sparkfun_5") (pin "1") (pinfunction "VCC_1") (pintype "passive"))
      (node (ref "74HC595Sparkfun_5") (pin "3") (pinfunction "/Reset_3") (pintype "passive"))
      (node (ref "74HC595Sparkfun_6") (pin "1") (pinfunction "VCC_1") (pintype "passive"))
      (node (ref "74HC595Sparkfun_6") (pin "3") (pinfunction "/Reset_3") (pintype "passive"))
      (node (ref "74HC595Sparkfun_7") (pin "1") (pinfunction "VCC_1") (pintype "passive"))
      (node (ref "74HC595Sparkfun_7") (pin "3") (pinfunction "/Reset_3") (pintype "passive"))
      (node (ref "74HC595Sparkfun_8") (pin "1") (pinfunction "VCC_1") (pintype "passive"))
      (node (ref "74HC595Sparkfun_8") (pin "3") (pinfunction "/Reset_3") (pintype "passive"))
      (node (ref "74HC595Sparkfun_9") (pin "1") (pinfunction "VCC_1") (pintype "passive"))
      (node (ref "74HC595Sparkfun_9") (pin "3") (pinfunction "/Reset_3") (pintype "passive"))
      (node (ref "Maître") (pin "5V") (pinfunction "5V_5V") (pintype "passive"))
    )
    (net (code "167") (name "unconnected-(74HC595Sparkfun_1-Clock-Pad12)") (class "Default")
      (node (ref "74HC595Sparkfun_1") (pin "12") (pinfunction "Clock_12") (pintype "passive"))
    )
    (net (code "168") (name "unconnected-(74HC595Sparkfun_1-GND-Pad9)") (class "Default")
      (node (ref "74HC595Sparkfun_1") (pin "9") (pinfunction "GND_9") (pintype "passive"))
    )
    (net (code "169") (name "unconnected-(74HC595Sparkfun_1-L_Clock-Pad13)") (class "Default")
      (node (ref "74HC595Sparkfun_1") (pin "13") (pinfunction "L_Clock_13") (pintype "passive"))
    )
    (net (code "170") (name "unconnected-(74HC595Sparkfun_1-VCC-Pad8)") (class "Default")
      (node (ref "74HC595Sparkfun_1") (pin "8") (pinfunction "VCC_8") (pintype "passive"))
    )
    (net (code "171") (name "unconnected-(74HC595Sparkfun_1-{slash}OE-Pad11)") (class "Default")
      (node (ref "74HC595Sparkfun_1") (pin "11") (pinfunction "/OE_11") (pintype "passive"))
    )
    (net (code "172") (name "unconnected-(74HC595Sparkfun_1-{slash}Reset-Pad10)") (class "Default")
      (node (ref "74HC595Sparkfun_1") (pin "10") (pinfunction "/Reset_10") (pintype "passive"))
    )
    (net (code "173") (name "unconnected-(74HC595Sparkfun_2-Clock-Pad12)") (class "Default")
      (node (ref "74HC595Sparkfun_2") (pin "12") (pinfunction "Clock_12") (pintype "passive"))
    )
    (net (code "174") (name "unconnected-(74HC595Sparkfun_2-GND-Pad9)") (class "Default")
      (node (ref "74HC595Sparkfun_2") (pin "9") (pinfunction "GND_9") (pintype "passive"))
    )
    (net (code "175") (name "unconnected-(74HC595Sparkfun_2-L_Clock-Pad13)") (class "Default")
      (node (ref "74HC595Sparkfun_2") (pin "13") (pinfunction "L_Clock_13") (pintype "passive"))
    )
    (net (code "176") (name "unconnected-(74HC595Sparkfun_2-VCC-Pad8)") (class "Default")
      (node (ref "74HC595Sparkfun_2") (pin "8") (pinfunction "VCC_8") (pintype "passive"))
    )
    (net (code "177") (name "unconnected-(74HC595Sparkfun_2-{slash}OE-Pad11)") (class "Default")
      (node (ref "74HC595Sparkfun_2") (pin "11") (pinfunction "/OE_11") (pintype "passive"))
    )
    (net (code "178") (name "unconnected-(74HC595Sparkfun_2-{slash}Reset-Pad10)") (class "Default")
      (node (ref "74HC595Sparkfun_2") (pin "10") (pinfunction "/Reset_10") (pintype "passive"))
    )
    (net (code "179") (name "unconnected-(74HC595Sparkfun_3-Clock-Pad12)") (class "Default")
      (node (ref "74HC595Sparkfun_3") (pin "12") (pinfunction "Clock_12") (pintype "passive"))
    )
    (net (code "180") (name "unconnected-(74HC595Sparkfun_3-GND-Pad9)") (class "Default")
      (node (ref "74HC595Sparkfun_3") (pin "9") (pinfunction "GND_9") (pintype "passive"))
    )
    (net (code "181") (name "unconnected-(74HC595Sparkfun_3-L_Clock-Pad13)") (class "Default")
      (node (ref "74HC595Sparkfun_3") (pin "13") (pinfunction "L_Clock_13") (pintype "passive"))
    )
    (net (code "182") (name "unconnected-(74HC595Sparkfun_3-VCC-Pad8)") (class "Default")
      (node (ref "74HC595Sparkfun_3") (pin "8") (pinfunction "VCC_8") (pintype "passive"))
    )
    (net (code "183") (name "unconnected-(74HC595Sparkfun_3-{slash}OE-Pad11)") (class "Default")
      (node (ref "74HC595Sparkfun_3") (pin "11") (pinfunction "/OE_11") (pintype "passive"))
    )
    (net (code "184") (name "unconnected-(74HC595Sparkfun_3-{slash}Reset-Pad10)") (class "Default")
      (node (ref "74HC595Sparkfun_3") (pin "10") (pinfunction "/Reset_10") (pintype "passive"))
    )
    (net (code "185") (name "unconnected-(74HC595Sparkfun_4-Clock-Pad12)") (class "Default")
      (node (ref "74HC595Sparkfun_4") (pin "12") (pinfunction "Clock_12") (pintype "passive"))
    )
    (net (code "186") (name "unconnected-(74HC595Sparkfun_4-GND-Pad9)") (class "Default")
      (node (ref "74HC595Sparkfun_4") (pin "9") (pinfunction "GND_9") (pintype "passive"))
    )
    (net (code "187") (name "unconnected-(74HC595Sparkfun_4-L_Clock-Pad13)") (class "Default")
      (node (ref "74HC595Sparkfun_4") (pin "13") (pinfunction "L_Clock_13") (pintype "passive"))
    )
    (net (code "188") (name "unconnected-(74HC595Sparkfun_4-VCC-Pad8)") (class "Default")
      (node (ref "74HC595Sparkfun_4") (pin "8") (pinfunction "VCC_8") (pintype "passive"))
    )
    (net (code "189") (name "unconnected-(74HC595Sparkfun_4-{slash}OE-Pad11)") (class "Default")
      (node (ref "74HC595Sparkfun_4") (pin "11") (pinfunction "/OE_11") (pintype "passive"))
    )
    (net (code "190") (name "unconnected-(74HC595Sparkfun_4-{slash}Reset-Pad10)") (class "Default")
      (node (ref "74HC595Sparkfun_4") (pin "10") (pinfunction "/Reset_10") (pintype "passive"))
    )
    (net (code "191") (name "unconnected-(74HC595Sparkfun_5-Clock-Pad12)") (class "Default")
      (node (ref "74HC595Sparkfun_5") (pin "12") (pinfunction "Clock_12") (pintype "passive"))
    )
    (net (code "192") (name "unconnected-(74HC595Sparkfun_5-GND-Pad9)") (class "Default")
      (node (ref "74HC595Sparkfun_5") (pin "9") (pinfunction "GND_9") (pintype "passive"))
    )
    (net (code "193") (name "unconnected-(74HC595Sparkfun_5-L_Clock-Pad13)") (class "Default")
      (node (ref "74HC595Sparkfun_5") (pin "13") (pinfunction "L_Clock_13") (pintype "passive"))
    )
    (net (code "194") (name "unconnected-(74HC595Sparkfun_5-VCC-Pad8)") (class "Default")
      (node (ref "74HC595Sparkfun_5") (pin "8") (pinfunction "VCC_8") (pintype "passive"))
    )
    (net (code "195") (name "unconnected-(74HC595Sparkfun_5-{slash}OE-Pad11)") (class "Default")
      (node (ref "74HC595Sparkfun_5") (pin "11") (pinfunction "/OE_11") (pintype "passive"))
    )
    (net (code "196") (name "unconnected-(74HC595Sparkfun_5-{slash}Reset-Pad10)") (class "Default")
      (node (ref "74HC595Sparkfun_5") (pin "10") (pinfunction "/Reset_10") (pintype "passive"))
    )
    (net (code "197") (name "unconnected-(74HC595Sparkfun_6-Clock-Pad12)") (class "Default")
      (node (ref "74HC595Sparkfun_6") (pin "12") (pinfunction "Clock_12") (pintype "passive"))
    )
    (net (code "198") (name "unconnected-(74HC595Sparkfun_6-GND-Pad9)") (class "Default")
      (node (ref "74HC595Sparkfun_6") (pin "9") (pinfunction "GND_9") (pintype "passive"))
    )
    (net (code "199") (name "unconnected-(74HC595Sparkfun_6-L_Clock-Pad13)") (class "Default")
      (node (ref "74HC595Sparkfun_6") (pin "13") (pinfunction "L_Clock_13") (pintype "passive"))
    )
    (net (code "200") (name "unconnected-(74HC595Sparkfun_6-VCC-Pad8)") (class "Default")
      (node (ref "74HC595Sparkfun_6") (pin "8") (pinfunction "VCC_8") (pintype "passive"))
    )
    (net (code "201") (name "unconnected-(74HC595Sparkfun_6-{slash}OE-Pad11)") (class "Default")
      (node (ref "74HC595Sparkfun_6") (pin "11") (pinfunction "/OE_11") (pintype "passive"))
    )
    (net (code "202") (name "unconnected-(74HC595Sparkfun_6-{slash}Reset-Pad10)") (class "Default")
      (node (ref "74HC595Sparkfun_6") (pin "10") (pinfunction "/Reset_10") (pintype "passive"))
    )
    (net (code "203") (name "unconnected-(74HC595Sparkfun_7-Clock-Pad12)") (class "Default")
      (node (ref "74HC595Sparkfun_7") (pin "12") (pinfunction "Clock_12") (pintype "passive"))
    )
    (net (code "204") (name "unconnected-(74HC595Sparkfun_7-GND-Pad9)") (class "Default")
      (node (ref "74HC595Sparkfun_7") (pin "9") (pinfunction "GND_9") (pintype "passive"))
    )
    (net (code "205") (name "unconnected-(74HC595Sparkfun_7-L_Clock-Pad13)") (class "Default")
      (node (ref "74HC595Sparkfun_7") (pin "13") (pinfunction "L_Clock_13") (pintype "passive"))
    )
    (net (code "206") (name "unconnected-(74HC595Sparkfun_7-VCC-Pad8)") (class "Default")
      (node (ref "74HC595Sparkfun_7") (pin "8") (pinfunction "VCC_8") (pintype "passive"))
    )
    (net (code "207") (name "unconnected-(74HC595Sparkfun_7-{slash}OE-Pad11)") (class "Default")
      (node (ref "74HC595Sparkfun_7") (pin "11") (pinfunction "/OE_11") (pintype "passive"))
    )
    (net (code "208") (name "unconnected-(74HC595Sparkfun_7-{slash}Reset-Pad10)") (class "Default")
      (node (ref "74HC595Sparkfun_7") (pin "10") (pinfunction "/Reset_10") (pintype "passive"))
    )
    (net (code "209") (name "unconnected-(74HC595Sparkfun_8-Clock-Pad12)") (class "Default")
      (node (ref "74HC595Sparkfun_8") (pin "12") (pinfunction "Clock_12") (pintype "passive"))
    )
    (net (code "210") (name "unconnected-(74HC595Sparkfun_8-GND-Pad9)") (class "Default")
      (node (ref "74HC595Sparkfun_8") (pin "9") (pinfunction "GND_9") (pintype "passive"))
    )
    (net (code "211") (name "unconnected-(74HC595Sparkfun_8-L_Clock-Pad13)") (class "Default")
      (node (ref "74HC595Sparkfun_8") (pin "13") (pinfunction "L_Clock_13") (pintype "passive"))
    )
    (net (code "212") (name "unconnected-(74HC595Sparkfun_8-VCC-Pad8)") (class "Default")
      (node (ref "74HC595Sparkfun_8") (pin "8") (pinfunction "VCC_8") (pintype "passive"))
    )
    (net (code "213") (name "unconnected-(74HC595Sparkfun_8-{slash}OE-Pad11)") (class "Default")
      (node (ref "74HC595Sparkfun_8") (pin "11") (pinfunction "/OE_11") (pintype "passive"))
    )
    (net (code "214") (name "unconnected-(74HC595Sparkfun_8-{slash}Reset-Pad10)") (class "Default")
      (node (ref "74HC595Sparkfun_8") (pin "10") (pinfunction "/Reset_10") (pintype "passive"))
    )
    (net (code "215") (name "unconnected-(74HC595Sparkfun_9-Clock-Pad12)") (class "Default")
      (node (ref "74HC595Sparkfun_9") (pin "12") (pinfunction "Clock_12") (pintype "passive"))
    )
    (net (code "216") (name "unconnected-(74HC595Sparkfun_9-GND-Pad9)") (class "Default")
      (node (ref "74HC595Sparkfun_9") (pin "9") (pinfunction "GND_9") (pintype "passive"))
    )
    (net (code "217") (name "unconnected-(74HC595Sparkfun_9-L_Clock-Pad13)") (class "Default")
      (node (ref "74HC595Sparkfun_9") (pin "13") (pinfunction "L_Clock_13") (pintype "passive"))
    )
    (net (code "218") (name "unconnected-(74HC595Sparkfun_9-VCC-Pad8)") (class "Default")
      (node (ref "74HC595Sparkfun_9") (pin "8") (pinfunction "VCC_8") (pintype "passive"))
    )
    (net (code "219") (name "unconnected-(74HC595Sparkfun_9-{slash}OE-Pad11)") (class "Default")
      (node (ref "74HC595Sparkfun_9") (pin "11") (pinfunction "/OE_11") (pintype "passive"))
    )
    (net (code "220") (name "unconnected-(74HC595Sparkfun_9-{slash}Reset-Pad10)") (class "Default")
      (node (ref "74HC595Sparkfun_9") (pin "10") (pinfunction "/Reset_10") (pintype "passive"))
    )
    (net (code "221") (name "unconnected-(74HC595Sparkfun_10-Clock-Pad12)") (class "Default")
      (node (ref "74HC595Sparkfun_10") (pin "12") (pinfunction "Clock_12") (pintype "passive"))
    )
    (net (code "222") (name "unconnected-(74HC595Sparkfun_10-D-Pad18)") (class "Default")
      (node (ref "74HC595Sparkfun_10") (pin "18") (pinfunction "D_18") (pintype "passive"))
    )
    (net (code "223") (name "unconnected-(74HC595Sparkfun_10-E-Pad19)") (class "Default")
      (node (ref "74HC595Sparkfun_10") (pin "19") (pinfunction "E_19") (pintype "passive"))
    )
    (net (code "224") (name "unconnected-(74HC595Sparkfun_10-F-Pad20)") (class "Default")
      (node (ref "74HC595Sparkfun_10") (pin "20") (pinfunction "F_20") (pintype "passive"))
    )
    (net (code "225") (name "unconnected-(74HC595Sparkfun_10-G-Pad21)") (class "Default")
      (node (ref "74HC595Sparkfun_10") (pin "21") (pinfunction "G_21") (pintype "passive"))
    )
    (net (code "226") (name "unconnected-(74HC595Sparkfun_10-GND-Pad9)") (class "Default")
      (node (ref "74HC595Sparkfun_10") (pin "9") (pinfunction "GND_9") (pintype "passive"))
    )
    (net (code "227") (name "unconnected-(74HC595Sparkfun_10-H-Pad22)") (class "Default")
      (node (ref "74HC595Sparkfun_10") (pin "22") (pinfunction "H_22") (pintype "passive"))
    )
    (net (code "228") (name "unconnected-(74HC595Sparkfun_10-L_Clock-Pad13)") (class "Default")
      (node (ref "74HC595Sparkfun_10") (pin "13") (pinfunction "L_Clock_13") (pintype "passive"))
    )
    (net (code "229") (name "unconnected-(74HC595Sparkfun_10-SER_OUT-Pad14)") (class "Default")
      (node (ref "74HC595Sparkfun_10") (pin "14") (pinfunction "SER_OUT_14") (pintype "passive"))
    )
    (net (code "230") (name "unconnected-(74HC595Sparkfun_10-VCC-Pad8)") (class "Default")
      (node (ref "74HC595Sparkfun_10") (pin "8") (pinfunction "VCC_8") (pintype "passive"))
    )
    (net (code "231") (name "unconnected-(74HC595Sparkfun_10-{slash}OE-Pad11)") (class "Default")
      (node (ref "74HC595Sparkfun_10") (pin "11") (pinfunction "/OE_11") (pintype "passive"))
    )
    (net (code "232") (name "unconnected-(74HC595Sparkfun_10-{slash}Reset-Pad10)") (class "Default")
      (node (ref "74HC595Sparkfun_10") (pin "10") (pinfunction "/Reset_10") (pintype "passive"))
    )
    (net (code "233") (name "unconnected-(Maître-*D3-PadD3)") (class "Default")
      (node (ref "Maître") (pin "D3") (pinfunction "*D3_D3") (pintype "passive"))
    )
    (net (code "234") (name "unconnected-(Maître-*D5-PadD5)") (class "Default")
      (node (ref "Maître") (pin "D5") (pinfunction "*D5_D5") (pintype "passive"))
    )
    (net (code "235") (name "unconnected-(Maître-*D6-PadD6)") (class "Default")
      (node (ref "Maître") (pin "D6") (pinfunction "*D6_D6") (pintype "passive"))
    )
    (net (code "236") (name "unconnected-(Maître-*D9-PadD9)") (class "Default")
      (node (ref "Maître") (pin "D9") (pinfunction "*D9_D9") (pintype "passive"))
    )
    (net (code "237") (name "unconnected-(Maître-*D10-PadD10)") (class "Default")
      (node (ref "Maître") (pin "D10") (pinfunction "*D10_D10") (pintype "passive"))
    )
    (net (code "238") (name "unconnected-(Maître-Pad3.3V)") (class "Default")
      (node (ref "Maître") (pin "3.3V") (pinfunction "3.3V_3.3V") (pintype "passive"))
    )
    (net (code "239") (name "unconnected-(Maître-PadA0)") (class "Default")
      (node (ref "Maître") (pin "A0") (pinfunction "A0_A0") (pintype "passive"))
    )
    (net (code "240") (name "unconnected-(Maître-PadA1)") (class "Default")
      (node (ref "Maître") (pin "A1") (pinfunction "A1_A1") (pintype "passive"))
    )
    (net (code "241") (name "unconnected-(Maître-PadA2)") (class "Default")
      (node (ref "Maître") (pin "A2") (pinfunction "A2_A2") (pintype "passive"))
    )
    (net (code "242") (name "unconnected-(Maître-PadA3)") (class "Default")
      (node (ref "Maître") (pin "A3") (pinfunction "A3_A3") (pintype "passive"))
    )
    (net (code "243") (name "unconnected-(Maître-PadAREF)") (class "Default")
      (node (ref "Maître") (pin "AREF") (pinfunction "AREF_AREF") (pintype "passive"))
    )
    (net (code "244") (name "unconnected-(Maître-PadD2)") (class "Default")
      (node (ref "Maître") (pin "D2") (pinfunction "D2_D2") (pintype "passive"))
    )
    (net (code "245") (name "unconnected-(Maître-PadD4)") (class "Default")
      (node (ref "Maître") (pin "D4") (pinfunction "D4_D4") (pintype "passive"))
    )
    (net (code "246") (name "unconnected-(Maître-PadD7)") (class "Default")
      (node (ref "Maître") (pin "D7") (pinfunction "D7_D7") (pintype "passive"))
    )
    (net (code "247") (name "unconnected-(Maître-PadD13)") (class "Default")
      (node (ref "Maître") (pin "D13") (pinfunction "D13_D13") (pintype "passive"))
    )
    (net (code "248") (name "unconnected-(Maître-PadGND@1)") (class "Default")
      (node (ref "Maître") (pin "GND@1") (pinfunction "GND@1_GND@1") (pintype "passive"))
    )
    (net (code "249") (name "unconnected-(Maître-PadGND@2)") (class "Default")
      (node (ref "Maître") (pin "GND@2") (pinfunction "GND@2_GND@2") (pintype "passive"))
    )
    (net (code "250") (name "unconnected-(Maître-PadIOREF)") (class "Default")
      (node (ref "Maître") (pin "IOREF") (pinfunction "IOREF_IOREF") (pintype "passive"))
    )
    (net (code "251") (name "unconnected-(Maître-PadRES)") (class "Default")
      (node (ref "Maître") (pin "RES") (pinfunction "RES_RES") (pintype "passive"))
    )
    (net (code "252") (name "unconnected-(Maître-PadRX)") (class "Default")
      (node (ref "Maître") (pin "RX") (pinfunction "RX_RX") (pintype "passive"))
    )
    (net (code "253") (name "unconnected-(Maître-PadSCL)") (class "Default")
      (node (ref "Maître") (pin "SCL") (pinfunction "SCL_SCL") (pintype "passive"))
    )
    (net (code "254") (name "unconnected-(Maître-PadSDA)") (class "Default")
      (node (ref "Maître") (pin "SDA") (pinfunction "SDA_SDA") (pintype "passive"))
    )
    (net (code "255") (name "unconnected-(Maître-PadTX)") (class "Default")
      (node (ref "Maître") (pin "TX") (pinfunction "TX_TX") (pintype "passive"))
    )
    (net (code "256") (name "unconnected-(Maître-PadVIN)") (class "Default")
      (node (ref "Maître") (pin "VIN") (pinfunction "VIN_VIN") (pintype "passive"))
    )
  )
)
